# FPGA.net
KiCad netlist of a schematic drawn in Altium Designer
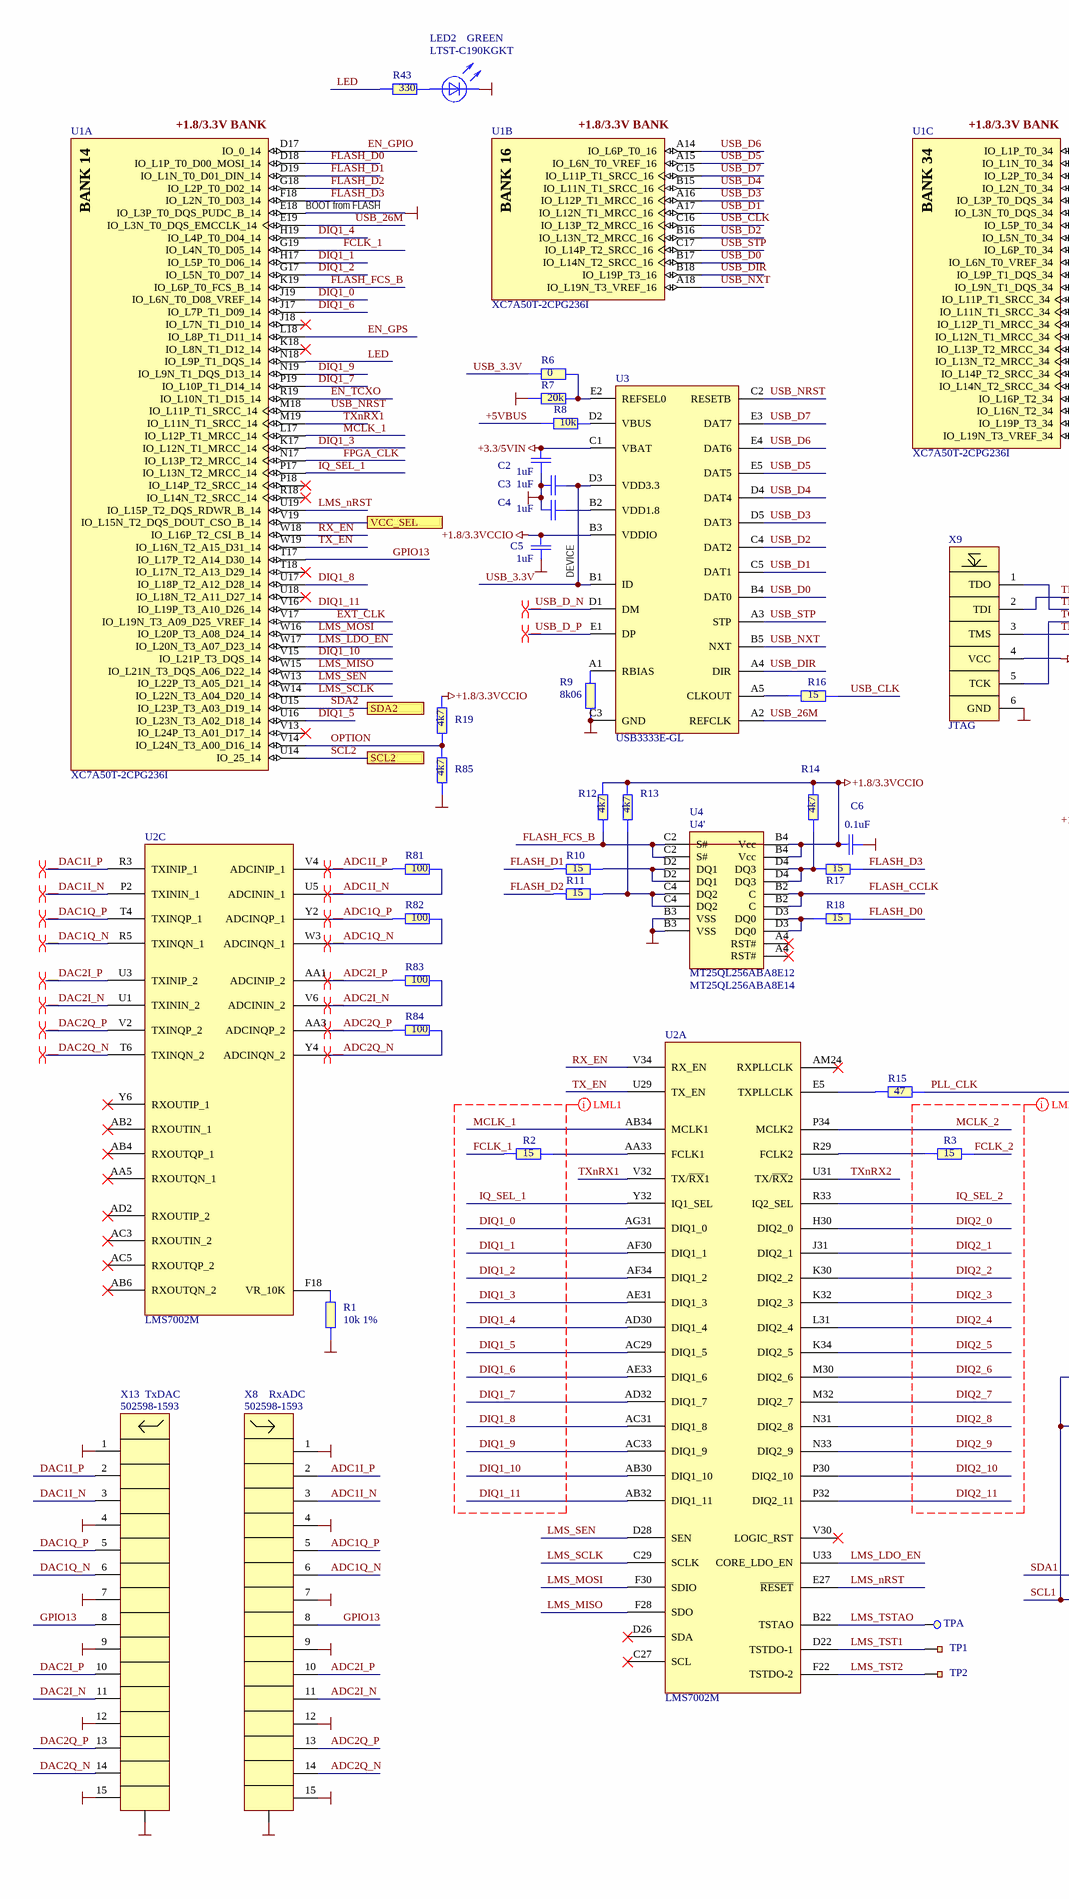
[diagram p0: FPGA.SchDoc, left]
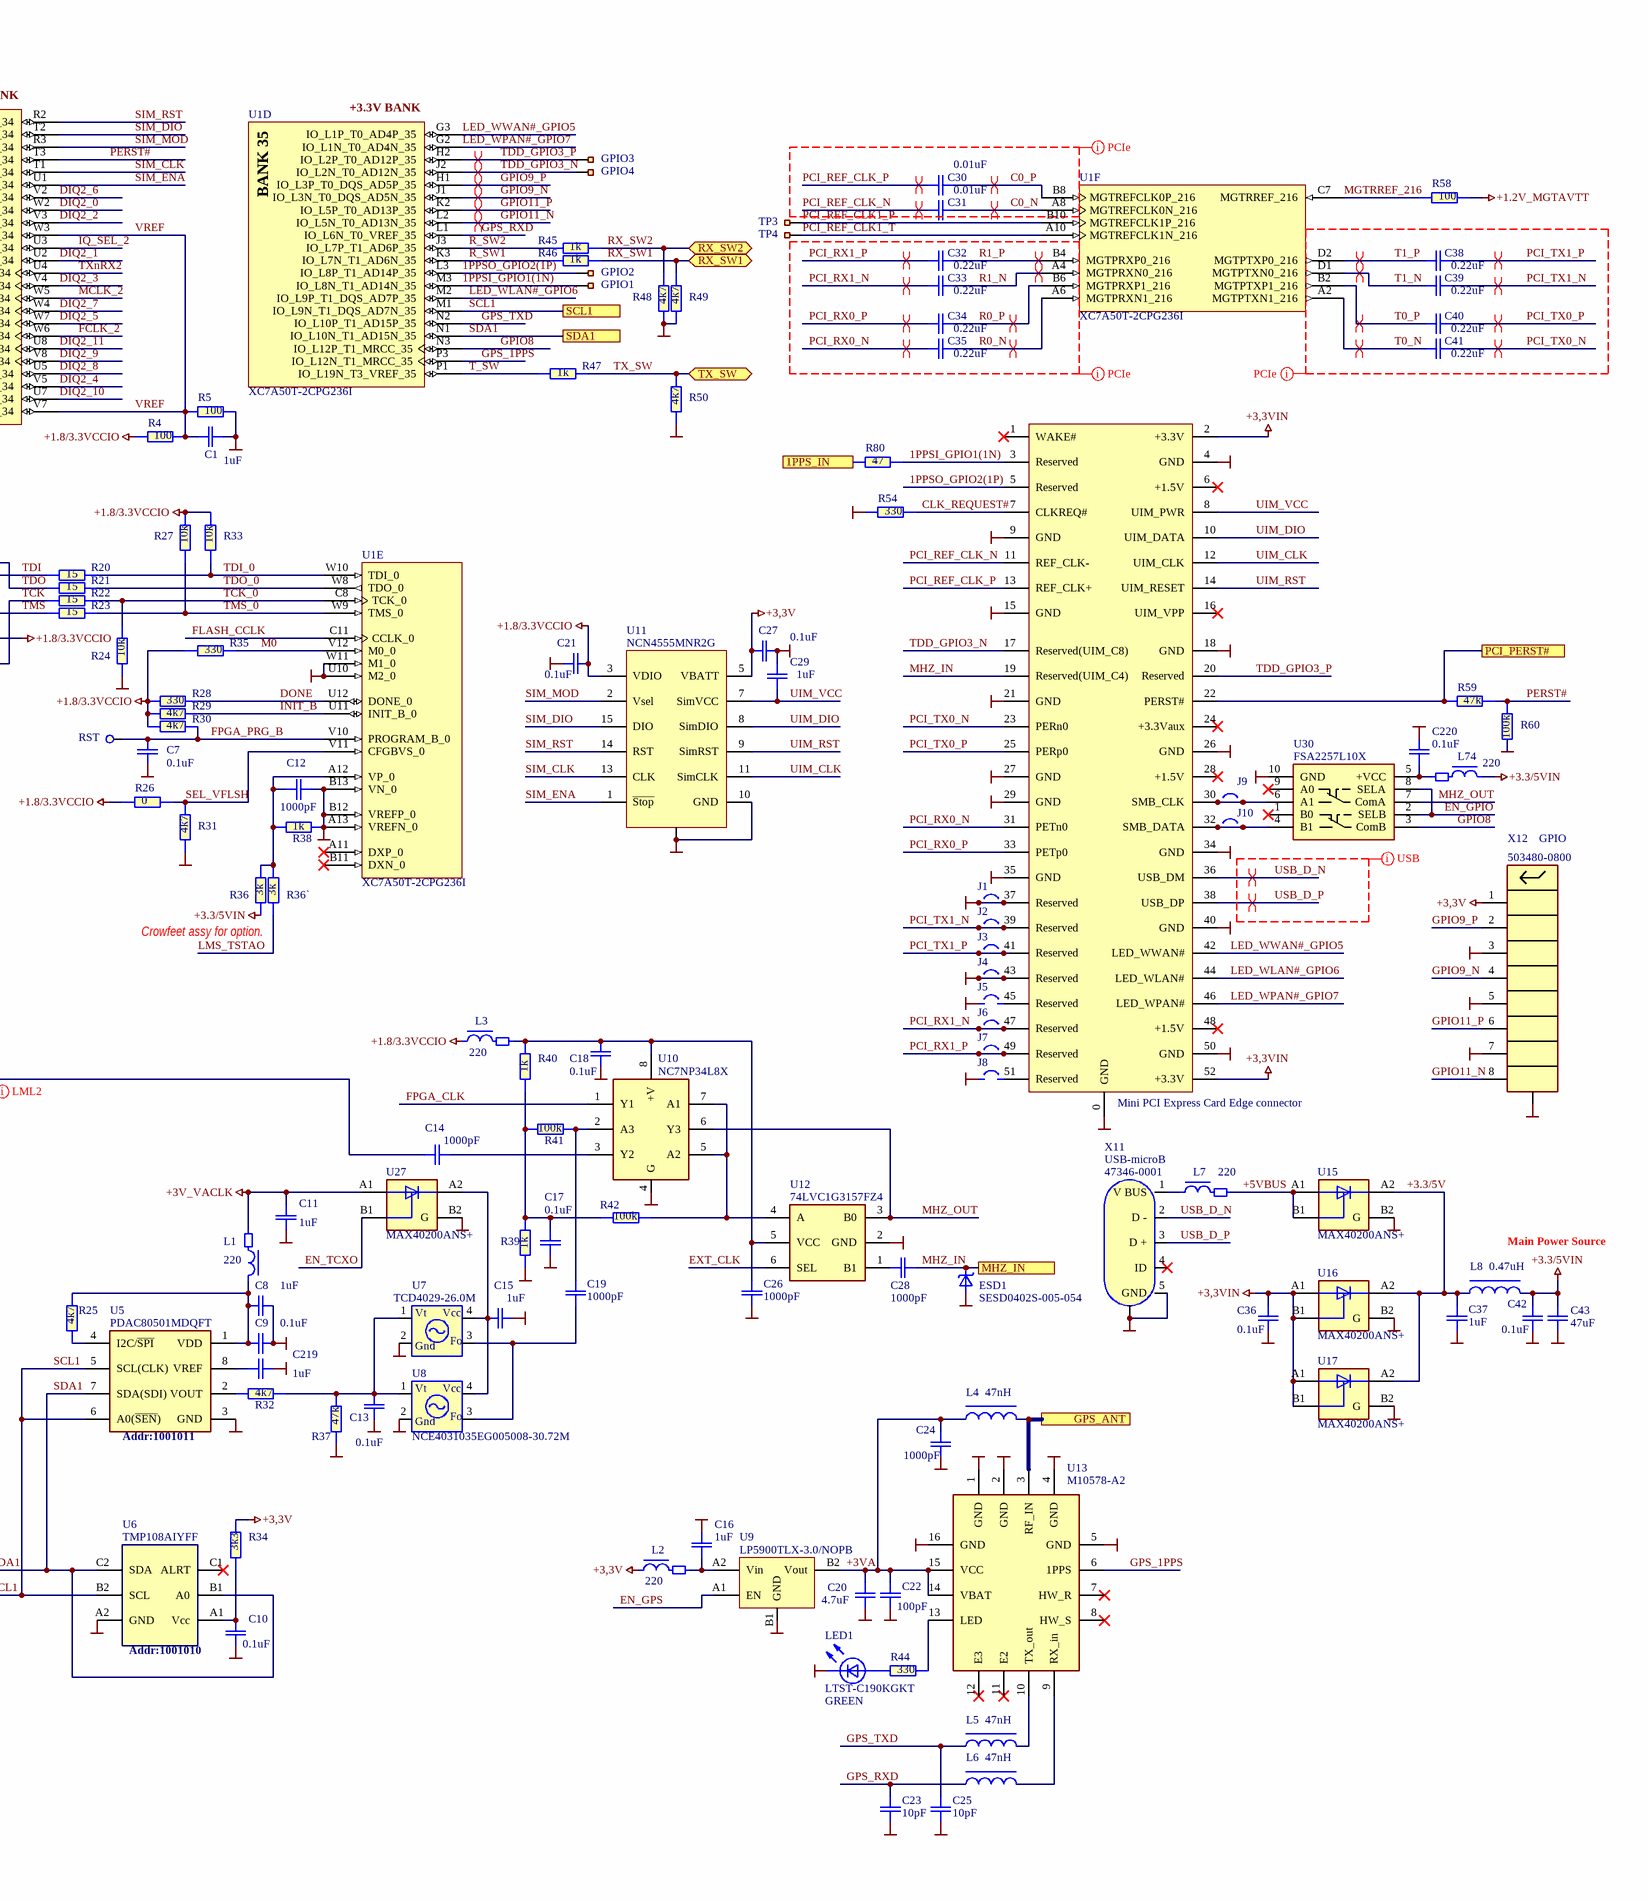
[diagram p1: FPGA.SchDoc, right]

(export (version "E")
  (design (tool "Eeschema 10.0.6"))
  (components
    (comp (ref "C1")
      (value "1uF")
      (footprint "C0402-cirq")
      (description "Capacitor")
      (fields (field (name "MANUFACTURER") "Any") (field (name "TOLERANCE") "20%"))
      (libsource (lib "Capacitors") (part "C0402"))
    )
    (comp (ref "C2")
      (value "1uF")
      (footprint "C0402-cirq")
      (description "Capacitor")
      (fields (field (name "MANUFACTURER") "Any") (field (name "TOLERANCE") "20%"))
      (libsource (lib "Capacitors") (part "C0402"))
    )
    (comp (ref "C3")
      (value "1uF")
      (footprint "C0402-cirq")
      (description "Capacitor")
      (fields (field (name "MANUFACTURER") "Any") (field (name "TOLERANCE") "20%"))
      (libsource (lib "Capacitors") (part "C0402"))
    )
    (comp (ref "C4")
      (value "1uF")
      (footprint "C0402-cirq")
      (description "Capacitor")
      (fields (field (name "MANUFACTURER") "Any") (field (name "TOLERANCE") "20%"))
      (libsource (lib "Capacitors") (part "C0402"))
    )
    (comp (ref "C5")
      (value "1uF")
      (footprint "C0402-cirq")
      (description "Capacitor")
      (fields (field (name "MANUFACTURER") "Any") (field (name "TOLERANCE") "20%"))
      (libsource (lib "Capacitors") (part "C0402"))
    )
    (comp (ref "C6")
      (value "0.1uF")
      (footprint "C0402-cirq")
      (description "Capacitor")
      (fields (field (name "MANUFACTURER") "Any") (field (name "TOLERANCE") "20%"))
      (libsource (lib "Capacitors") (part "C0402"))
    )
    (comp (ref "C7")
      (value "0.1uF")
      (footprint "C0402-cirq")
      (description "Capacitor")
      (fields (field (name "MANUFACTURER") "Any") (field (name "TOLERANCE") "20%"))
      (libsource (lib "Capacitors") (part "C0402"))
    )
    (comp (ref "C8")
      (value "1uF")
      (footprint "C0402-cirq")
      (description "Capacitor")
      (fields (field (name "MANUFACTURER") "Any") (field (name "TOLERANCE") "20%"))
      (libsource (lib "Capacitors") (part "C0402"))
    )
    (comp (ref "C9")
      (value "0.1uF")
      (footprint "C0402-cirq")
      (description "Capacitor")
      (fields (field (name "MANUFACTURER") "Any") (field (name "TOLERANCE") "20%"))
      (libsource (lib "Capacitors") (part "C0402"))
    )
    (comp (ref "C10")
      (value "0.1uF")
      (footprint "C0402-cirq")
      (description "Capacitor")
      (fields (field (name "MANUFACTURER") "Any") (field (name "TOLERANCE") "20%"))
      (libsource (lib "Capacitors") (part "C0402"))
    )
    (comp (ref "C11")
      (value "1uF")
      (footprint "C0402-cirq")
      (description "Capacitor")
      (fields (field (name "MANUFACTURER") "Any") (field (name "TOLERANCE") "20%"))
      (libsource (lib "Capacitors") (part "C0402"))
    )
    (comp (ref "C12")
      (value "1000pF")
      (footprint "C0402-cirq")
      (description "Capacitor")
      (fields (field (name "MANUFACTURER") "Any") (field (name "TOLERANCE") "10%"))
      (libsource (lib "Capacitors") (part "C0402"))
    )
    (comp (ref "C13")
      (value "0.1uF")
      (footprint "C0402-cirq")
      (description "Capacitor")
      (fields (field (name "MANUFACTURER") "Any") (field (name "TOLERANCE") "20%"))
      (libsource (lib "Capacitors") (part "C0402"))
    )
    (comp (ref "C14")
      (value "1000pF")
      (footprint "C0402-cirq")
      (description "Capacitor")
      (fields (field (name "MANUFACTURER") "Any") (field (name "TOLERANCE") "10%"))
      (libsource (lib "Capacitors") (part "C0402"))
    )
    (comp (ref "C15")
      (value "1uF")
      (footprint "C0402-cirq")
      (description "Capacitor")
      (fields (field (name "MANUFACTURER") "Any") (field (name "TOLERANCE") "20%"))
      (libsource (lib "Capacitors") (part "C0402"))
    )
    (comp (ref "C16")
      (value "1uF")
      (footprint "C0402-cirq")
      (description "Capacitor")
      (fields (field (name "MANUFACTURER") "Any") (field (name "TOLERANCE") "20%"))
      (libsource (lib "Capacitors") (part "C0402"))
    )
    (comp (ref "C17")
      (value "0.1uF")
      (footprint "C0402-cirq")
      (description "Capacitor")
      (fields (field (name "MANUFACTURER") "Any") (field (name "TOLERANCE") "20%"))
      (libsource (lib "Capacitors") (part "C0402"))
    )
    (comp (ref "C18")
      (value "0.1uF")
      (footprint "C0402-cirq")
      (description "Capacitor")
      (fields (field (name "MANUFACTURER") "Any") (field (name "TOLERANCE") "20%"))
      (libsource (lib "Capacitors") (part "C0402"))
    )
    (comp (ref "C19")
      (value "1000pF")
      (footprint "C0402-cirq")
      (description "Capacitor")
      (fields (field (name "MANUFACTURER") "Any") (field (name "TOLERANCE") "10%"))
      (libsource (lib "Capacitors") (part "C0402"))
    )
    (comp (ref "C20")
      (value "4.7uF")
      (footprint "C0402-cirq")
      (description "Capacitor")
      (fields (field (name "MANUFACTURER") "Any") (field (name "TOLERANCE") "20%"))
      (libsource (lib "Capacitors") (part "C0402"))
    )
    (comp (ref "C21")
      (value "0.1uF")
      (footprint "C0402-cirq")
      (description "Capacitor")
      (fields (field (name "MANUFACTURER") "Any") (field (name "TOLERANCE") "20%"))
      (libsource (lib "Capacitors") (part "C0402"))
    )
    (comp (ref "C22")
      (value "100pF")
      (footprint "C0402-cirq")
      (description "Capacitor")
      (fields (field (name "MANUFACTURER") "Any") (field (name "TOLERANCE") "20%"))
      (libsource (lib "Capacitors") (part "C0402"))
    )
    (comp (ref "C23")
      (value "10pF")
      (footprint "C0402-cirq")
      (description "Capacitor")
      (fields (field (name "MANUFACTURER") "Any") (field (name "TOLERANCE") "20%"))
      (libsource (lib "Capacitors") (part "C0402"))
    )
    (comp (ref "C24")
      (value "1000pF")
      (footprint "C0402-cirq")
      (description "Capacitor")
      (fields (field (name "MANUFACTURER") "Any") (field (name "TOLERANCE") "10%"))
      (libsource (lib "Capacitors") (part "C0402"))
    )
    (comp (ref "C25")
      (value "10pF")
      (footprint "C0402-cirq")
      (description "Capacitor")
      (fields (field (name "MANUFACTURER") "Any") (field (name "TOLERANCE") "20%"))
      (libsource (lib "Capacitors") (part "C0402"))
    )
    (comp (ref "C26")
      (value "1000pF")
      (footprint "C0402-cirq")
      (description "Capacitor")
      (fields (field (name "MANUFACTURER") "Any") (field (name "TOLERANCE") "10%"))
      (libsource (lib "Capacitors") (part "C0402"))
    )
    (comp (ref "C27")
      (value "0.1uF")
      (footprint "C0402-cirq")
      (description "Capacitor")
      (fields (field (name "MANUFACTURER") "Any") (field (name "TOLERANCE") "20%"))
      (libsource (lib "Capacitors") (part "C0402"))
    )
    (comp (ref "C28")
      (value "1000pF")
      (footprint "C0402-cirq")
      (description "Capacitor")
      (fields (field (name "MANUFACTURER") "Any") (field (name "TOLERANCE") "10%"))
      (libsource (lib "Capacitors") (part "C0402"))
    )
    (comp (ref "C29")
      (value "1uF")
      (footprint "C0402-cirq")
      (description "Capacitor")
      (fields (field (name "MANUFACTURER") "Any") (field (name "TOLERANCE") "20%"))
      (libsource (lib "Capacitors") (part "C0402"))
    )
    (comp (ref "C30")
      (value "0.01uF")
      (footprint "C0402-cirq")
      (description "Capacitor")
      (fields (field (name "MANUFACTURER") "Any") (field (name "TOLERANCE") "10%"))
      (libsource (lib "Capacitors") (part "C0402"))
    )
    (comp (ref "C31")
      (value "0.01uF")
      (footprint "C0402-cirq")
      (description "Capacitor")
      (fields (field (name "MANUFACTURER") "Any") (field (name "TOLERANCE") "10%"))
      (libsource (lib "Capacitors") (part "C0402"))
    )
    (comp (ref "C32")
      (value "0.22uF")
      (footprint "C0402-cirq")
      (description "Capacitor")
      (fields (field (name "MANUFACTURER") "Any") (field (name "TOLERANCE") "20%"))
      (libsource (lib "Capacitors") (part "C0402"))
    )
    (comp (ref "C33")
      (value "0.22uF")
      (footprint "C0402-cirq")
      (description "Capacitor")
      (fields (field (name "MANUFACTURER") "Any") (field (name "TOLERANCE") "20%"))
      (libsource (lib "Capacitors") (part "C0402"))
    )
    (comp (ref "C34")
      (value "0.22uF")
      (footprint "C0402-cirq")
      (description "Capacitor")
      (fields (field (name "MANUFACTURER") "Any") (field (name "TOLERANCE") "20%"))
      (libsource (lib "Capacitors") (part "C0402"))
    )
    (comp (ref "C35")
      (value "0.22uF")
      (footprint "C0402-cirq")
      (description "Capacitor")
      (fields (field (name "MANUFACTURER") "Any") (field (name "TOLERANCE") "20%"))
      (libsource (lib "Capacitors") (part "C0402"))
    )
    (comp (ref "C36")
      (value "0.1uF")
      (footprint "C0402-cirq")
      (description "Capacitor")
      (fields (field (name "MANUFACTURER") "Any") (field (name "TOLERANCE") "20%"))
      (libsource (lib "Capacitors") (part "C0402"))
    )
    (comp (ref "C37")
      (value "1uF")
      (footprint "C0402-cirq")
      (description "Capacitor")
      (fields (field (name "MANUFACTURER") "Any") (field (name "TOLERANCE") "20%"))
      (libsource (lib "Capacitors") (part "C0402"))
    )
    (comp (ref "C38")
      (value "0.22uF")
      (footprint "C0402-cirq")
      (description "Capacitor")
      (fields (field (name "MANUFACTURER") "Any") (field (name "TOLERANCE") "20%"))
      (libsource (lib "Capacitors") (part "C0402"))
    )
    (comp (ref "C39")
      (value "0.22uF")
      (footprint "C0402-cirq")
      (description "Capacitor")
      (fields (field (name "MANUFACTURER") "Any") (field (name "TOLERANCE") "20%"))
      (libsource (lib "Capacitors") (part "C0402"))
    )
    (comp (ref "C40")
      (value "0.22uF")
      (footprint "C0402-cirq")
      (description "Capacitor")
      (fields (field (name "MANUFACTURER") "Any") (field (name "TOLERANCE") "20%"))
      (libsource (lib "Capacitors") (part "C0402"))
    )
    (comp (ref "C41")
      (value "0.22uF")
      (footprint "C0402-cirq")
      (description "Capacitor")
      (fields (field (name "MANUFACTURER") "Any") (field (name "TOLERANCE") "20%"))
      (libsource (lib "Capacitors") (part "C0402"))
    )
    (comp (ref "C42")
      (value "0.1uF")
      (footprint "C0402-cirq")
      (description "Capacitor")
      (fields (field (name "MANUFACTURER") "Any") (field (name "TOLERANCE") "20%"))
      (libsource (lib "Capacitors") (part "C0402"))
    )
    (comp (ref "C43")
      (value "47uF")
      (footprint "C0603 tall")
      (description "Capacitor")
      (fields (field (name "MANUFACTURER") "MuRata") (field (name "TOLERANCE") "20%"))
      (libsource (lib "Andy") (part "C0603-TALL"))
    )
    (comp (ref "C219")
      (value "1uF")
      (footprint "C0402-cirq")
      (description "Capacitor")
      (fields (field (name "MANUFACTURER") "Any") (field (name "TOLERANCE") "20%"))
      (libsource (lib "Capacitors") (part "C0402"))
    )
    (comp (ref "C220")
      (value "0.1uF")
      (footprint "C0402-cirq")
      (description "Capacitor")
      (fields (field (name "MANUFACTURER") "Any") (field (name "TOLERANCE") "20%"))
      (libsource (lib "Capacitors") (part "C0402"))
    )
    (comp (ref "ESD1")
      (value "SESD0402S-005-054")
      (footprint "SESD0402-Phillips")
      (description "ESD diod unidirectional")
      (fields (field (name "MANUFACTURER") "Tyco Electronics Corp"))
      (libsource (lib "Andy") (part "SESD0402S"))
    )
    (comp (ref "GPIO1")
      (value "~")
      (footprint "KP-C_d1mm")
      (fields (field (name "MANUFACTURER") "PCB"))
      (libsource (lib "") (part "KP40X40_1"))
    )
    (comp (ref "GPIO2")
      (value "~")
      (footprint "KP-C_d1mm")
      (fields (field (name "MANUFACTURER") "PCB"))
      (libsource (lib "") (part "KP40X40_1"))
    )
    (comp (ref "GPIO3")
      (value "~")
      (footprint "KP-C_d1mm")
      (fields (field (name "MANUFACTURER") "PCB"))
      (libsource (lib "") (part "KP40X40_1"))
    )
    (comp (ref "GPIO4")
      (value "~")
      (footprint "KP-C_d1mm")
      (fields (field (name "MANUFACTURER") "PCB"))
      (libsource (lib "") (part "KP40X40_1"))
    )
    (comp (ref "J1")
      (value "~")
      (footprint "Andy:Jumper solder")
      (description "Manually soldered jumper")
      (fields (field (name "MANUFACTURER") "DIY"))
      (libsource (lib "Andy") (part "JUMPER PCB"))
    )
    (comp (ref "J2")
      (value "~")
      (footprint "Andy:Jumper solder")
      (description "Manually soldered jumper")
      (fields (field (name "MANUFACTURER") "DIY"))
      (libsource (lib "Andy") (part "JUMPER PCB"))
    )
    (comp (ref "J3")
      (value "~")
      (footprint "Andy:Jumper solder")
      (description "Manually soldered jumper")
      (fields (field (name "MANUFACTURER") "DIY"))
      (libsource (lib "Andy") (part "JUMPER PCB"))
    )
    (comp (ref "J4")
      (value "~")
      (footprint "Andy:Jumper solder")
      (description "Manually soldered jumper")
      (fields (field (name "MANUFACTURER") "DIY"))
      (libsource (lib "Andy") (part "JUMPER PCB"))
    )
    (comp (ref "J5")
      (value "~")
      (footprint "Andy:Jumper solder")
      (description "Manually soldered jumper")
      (fields (field (name "MANUFACTURER") "DIY"))
      (libsource (lib "Andy") (part "JUMPER PCB"))
    )
    (comp (ref "J6")
      (value "~")
      (footprint "Andy:Jumper solder")
      (description "Manually soldered jumper")
      (fields (field (name "MANUFACTURER") "DIY"))
      (libsource (lib "Andy") (part "JUMPER PCB"))
    )
    (comp (ref "J7")
      (value "~")
      (footprint "Andy:Jumper solder")
      (description "Manually soldered jumper")
      (fields (field (name "MANUFACTURER") "DIY"))
      (libsource (lib "Andy") (part "JUMPER PCB"))
    )
    (comp (ref "J8")
      (value "~")
      (footprint "Andy:Jumper solder")
      (description "Manually soldered jumper")
      (fields (field (name "MANUFACTURER") "DIY"))
      (libsource (lib "Andy") (part "JUMPER PCB"))
    )
    (comp (ref "J9")
      (value "~")
      (footprint "Andy:Jumper solder")
      (description "Manually soldered jumper")
      (fields (field (name "MANUFACTURER") "DIY"))
      (libsource (lib "Andy") (part "JUMPER PCB"))
    )
    (comp (ref "J10")
      (value "~")
      (footprint "Andy:Jumper solder")
      (description "Manually soldered jumper")
      (fields (field (name "MANUFACTURER") "DIY"))
      (libsource (lib "Andy") (part "JUMPER PCB"))
    )
    (comp (ref "L1")
      (value "220")
      (footprint "BEAD0402-Phillips")
      (description "Ferrite bead EMIFIL")
      (fields (field (name "MANUFACTURER") "MURATA"))
      (libsource (lib "") (part "EMI BLM15_1"))
    )
    (comp (ref "L2")
      (value "220")
      (footprint "BEAD0402-Phillips")
      (description "Ferrite bead EMIFIL")
      (fields (field (name "MANUFACTURER") "MURATA"))
      (libsource (lib "Andy") (part "EMI BLM15"))
    )
    (comp (ref "L3")
      (value "220")
      (footprint "BEAD0402-Phillips")
      (description "Ferrite bead EMIFIL")
      (fields (field (name "MANUFACTURER") "MURATA"))
      (libsource (lib "Andy") (part "EMI BLM15"))
    )
    (comp (ref "L4")
      (value "47nH")
      (footprint "COIL0402-Phillips")
      (description "Coil wire wound")
      (fields (field (name "MANUFACTURER") "MuRata") (field (name "TOLERANCE") "±5%"))
      (libsource (lib "Andy") (part "L-LQW15"))
    )
    (comp (ref "L5")
      (value "47nH")
      (footprint "COIL0402-Phillips")
      (description "Coil wire wound")
      (fields (field (name "MANUFACTURER") "MuRata") (field (name "TOLERANCE") "±5%"))
      (libsource (lib "Andy") (part "L-LQW15"))
    )
    (comp (ref "L6")
      (value "47nH")
      (footprint "COIL0402-Phillips")
      (description "Coil wire wound")
      (fields (field (name "MANUFACTURER") "MuRata") (field (name "TOLERANCE") "±5%"))
      (libsource (lib "Andy") (part "L-LQW15"))
    )
    (comp (ref "L7")
      (value "220")
      (footprint "BEAD0402-Phillips")
      (description "Ferrite bead EMIFIL")
      (fields (field (name "MANUFACTURER") "MURATA"))
      (libsource (lib "Andy") (part "EMI BLM15"))
    )
    (comp (ref "L8")
      (value "0.47uH")
      (footprint "L-VLS201610HBX")
      (description "Coil")
      (fields (field (name "MANUFACTURER") "TDK"))
      (libsource (lib "Andy") (part "L-VLS20161xHBX-1"))
    )
    (comp (ref "L74")
      (value "220")
      (footprint "BEAD0402-Phillips")
      (description "Ferrite bead EMIFIL")
      (fields (field (name "MANUFACTURER") "MURATA"))
      (libsource (lib "") (part "EMI BLM15_1"))
    )
    (comp (ref "LED1")
      (value "LTST-C190KGKT")
      (footprint "Andy:LED-0603GR")
      (description "LED GREEN")
      (fields (field (name "MANUFACTURER") "Lite-On Inc") (field (name "MISC") "GREEN"))
      (libsource (lib "Andy") (part "LED0603GR_Lite-On"))
    )
    (comp (ref "LED2")
      (value "LTST-C190KGKT")
      (footprint "Andy:LED-0603GR")
      (description "LED GREEN")
      (fields (field (name "MANUFACTURER") "Lite-On Inc") (field (name "MISC") "GREEN"))
      (libsource (lib "Andy") (part "LED0603GR_Lite-On"))
    )
    (comp (ref "R1")
      (value "10k 1%")
      (footprint "R0402-Phillips")
      (description "Resistor")
      (fields (field (name "MANUFACTURER") "BOURNS") (field (name "TOLERANCE") "1%"))
      (libsource (lib "") (part "R0402_2"))
    )
    (comp (ref "R2")
      (value "15")
      (footprint "R0402-Phillips")
      (description "Resistor")
      (fields (field (name "MANUFACTURER") "BOURNS") (field (name "TOLERANCE") "5%"))
      (libsource (lib "Andy") (part "R0402"))
    )
    (comp (ref "R3")
      (value "15")
      (footprint "R0402-Phillips")
      (description "Resistor")
      (fields (field (name "MANUFACTURER") "BOURNS") (field (name "TOLERANCE") "5%"))
      (libsource (lib "Andy") (part "R0402"))
    )
    (comp (ref "R4")
      (value "100")
      (footprint "R0402-Phillips")
      (description "Resistor")
      (fields (field (name "MANUFACTURER") "BOURNS") (field (name "TOLERANCE") "5%"))
      (libsource (lib "Andy") (part "R0402"))
    )
    (comp (ref "R5")
      (value "100")
      (footprint "R0402-Phillips")
      (description "Resistor")
      (fields (field (name "MANUFACTURER") "BOURNS") (field (name "TOLERANCE") "5%"))
      (libsource (lib "Andy") (part "R0402"))
    )
    (comp (ref "R6")
      (value "0")
      (footprint "R0402-Phillips")
      (description "Resistor")
      (fields (field (name "MANUFACTURER") "BOURNS") (field (name "TOLERANCE") "5%"))
      (libsource (lib "Andy") (part "R0402"))
    )
    (comp (ref "R7")
      (value "20k")
      (footprint "R0402-Phillips")
      (description "Resistor")
      (fields (field (name "MANUFACTURER") "BOURNS") (field (name "TOLERANCE") "5%"))
      (libsource (lib "Andy") (part "R0402"))
    )
    (comp (ref "R8")
      (value "10k")
      (footprint "R0402-Phillips")
      (description "Resistor")
      (fields (field (name "MANUFACTURER") "BOURNS") (field (name "TOLERANCE") "5%"))
      (libsource (lib "Andy") (part "R0402"))
    )
    (comp (ref "R9")
      (value "8k06")
      (footprint "R0402-Phillips")
      (description "Resistor")
      (fields (field (name "MANUFACTURER") "Panasonic") (field (name "TOLERANCE") "0.5%"))
      (libsource (lib "") (part "R0402_2"))
    )
    (comp (ref "R10")
      (value "15")
      (footprint "R0402-Phillips")
      (description "Resistor")
      (fields (field (name "MANUFACTURER") "BOURNS") (field (name "TOLERANCE") "5%"))
      (libsource (lib "") (part "R0402_3"))
    )
    (comp (ref "R11")
      (value "15")
      (footprint "R0402-Phillips")
      (description "Resistor")
      (fields (field (name "MANUFACTURER") "BOURNS") (field (name "TOLERANCE") "5%"))
      (libsource (lib "") (part "R0402_3"))
    )
    (comp (ref "R12")
      (value "4k7")
      (footprint "R0402-Phillips")
      (description "Resistor")
      (fields (field (name "MANUFACTURER") "BOURNS") (field (name "TOLERANCE") "5%"))
      (libsource (lib "") (part "R0402_1"))
    )
    (comp (ref "R13")
      (value "4k7")
      (footprint "R0402-Phillips")
      (description "Resistor")
      (fields (field (name "MANUFACTURER") "BOURNS") (field (name "TOLERANCE") "5%"))
      (libsource (lib "") (part "R0402_1"))
    )
    (comp (ref "R14")
      (value "4k7")
      (footprint "R0402-Phillips")
      (description "Resistor")
      (fields (field (name "MANUFACTURER") "BOURNS") (field (name "TOLERANCE") "5%"))
      (libsource (lib "") (part "R0402_1"))
    )
    (comp (ref "R15")
      (value "47")
      (footprint "R0402-Phillips")
      (description "Resistor")
      (fields (field (name "MANUFACTURER") "BOURNS") (field (name "TOLERANCE") "5%"))
      (libsource (lib "Andy") (part "R0402"))
    )
    (comp (ref "R16")
      (value "15")
      (footprint "R0402-Phillips")
      (description "Resistor")
      (fields (field (name "MANUFACTURER") "BOURNS") (field (name "TOLERANCE") "5%"))
      (libsource (lib "Andy") (part "R0402"))
    )
    (comp (ref "R17")
      (value "15")
      (footprint "R0402-Phillips")
      (description "Resistor")
      (fields (field (name "MANUFACTURER") "BOURNS") (field (name "TOLERANCE") "5%"))
      (libsource (lib "") (part "R0402_3"))
    )
    (comp (ref "R18")
      (value "15")
      (footprint "R0402-Phillips")
      (description "Resistor")
      (fields (field (name "MANUFACTURER") "BOURNS") (field (name "TOLERANCE") "5%"))
      (libsource (lib "") (part "R0402_3"))
    )
    (comp (ref "R19")
      (value "4k7")
      (footprint "R0402-Phillips")
      (description "Resistor")
      (fields (field (name "MANUFACTURER") "BOURNS") (field (name "TOLERANCE") "5%"))
      (libsource (lib "") (part "R0402_1"))
    )
    (comp (ref "R20")
      (value "15")
      (footprint "R0402-Phillips")
      (description "Resistor")
      (fields (field (name "MANUFACTURER") "BOURNS") (field (name "TOLERANCE") "5%"))
      (libsource (lib "Andy") (part "R0402"))
    )
    (comp (ref "R21")
      (value "15")
      (footprint "R0402-Phillips")
      (description "Resistor")
      (fields (field (name "MANUFACTURER") "BOURNS") (field (name "TOLERANCE") "5%"))
      (libsource (lib "Andy") (part "R0402"))
    )
    (comp (ref "R22")
      (value "15")
      (footprint "R0402-Phillips")
      (description "Resistor")
      (fields (field (name "MANUFACTURER") "BOURNS") (field (name "TOLERANCE") "5%"))
      (libsource (lib "Andy") (part "R0402"))
    )
    (comp (ref "R23")
      (value "15")
      (footprint "R0402-Phillips")
      (description "Resistor")
      (fields (field (name "MANUFACTURER") "BOURNS") (field (name "TOLERANCE") "5%"))
      (libsource (lib "Andy") (part "R0402"))
    )
    (comp (ref "R24")
      (value "10k")
      (footprint "R0402-Phillips")
      (description "Resistor")
      (fields (field (name "MANUFACTURER") "BOURNS") (field (name "TOLERANCE") "5%"))
      (libsource (lib "") (part "R0402_1"))
    )
    (comp (ref "R25")
      (value "4k7")
      (footprint "R0402-Phillips")
      (description "Resistor")
      (fields (field (name "MANUFACTURER") "BOURNS") (field (name "TOLERANCE") "5%"))
      (libsource (lib "") (part "R0402_2"))
    )
    (comp (ref "R26")
      (value "0")
      (footprint "R0402-Phillips")
      (description "Resistor")
      (fields (field (name "MANUFACTURER") "BOURNS") (field (name "TOLERANCE") "5%"))
      (libsource (lib "Andy") (part "R0402"))
    )
    (comp (ref "R27")
      (value "10k")
      (footprint "R0402-Phillips")
      (description "Resistor")
      (fields (field (name "MANUFACTURER") "BOURNS") (field (name "TOLERANCE") "5%"))
      (libsource (lib "") (part "R0402_1"))
    )
    (comp (ref "R28")
      (value "330")
      (footprint "R0402-Phillips")
      (description "Resistor")
      (fields (field (name "MANUFACTURER") "BOURNS") (field (name "TOLERANCE") "5%"))
      (libsource (lib "Andy") (part "R0402"))
    )
    (comp (ref "R29")
      (value "4k7")
      (footprint "R0402-Phillips")
      (description "Resistor")
      (fields (field (name "MANUFACTURER") "BOURNS") (field (name "TOLERANCE") "5%"))
      (libsource (lib "Andy") (part "R0402"))
    )
    (comp (ref "R30")
      (value "4k7")
      (footprint "R0402-Phillips")
      (description "Resistor")
      (fields (field (name "MANUFACTURER") "BOURNS") (field (name "TOLERANCE") "5%"))
      (libsource (lib "Andy") (part "R0402"))
    )
    (comp (ref "R31")
      (value "4k7")
      (footprint "R0402-Phillips")
      (description "Resistor")
      (fields (field (name "MANUFACTURER") "BOURNS") (field (name "TOLERANCE") "5%"))
      (libsource (lib "") (part "R0402_2"))
    )
    (comp (ref "R32")
      (value "4k7")
      (footprint "R0402-Phillips")
      (description "Resistor")
      (fields (field (name "MANUFACTURER") "BOURNS") (field (name "TOLERANCE") "5%"))
      (libsource (lib "Andy") (part "R0402"))
    )
    (comp (ref "R33")
      (value "10k")
      (footprint "R0402-Phillips")
      (description "Resistor")
      (fields (field (name "MANUFACTURER") "BOURNS") (field (name "TOLERANCE") "5%"))
      (libsource (lib "") (part "R0402_1"))
    )
    (comp (ref "R34")
      (value "3k3")
      (footprint "R0402-Phillips")
      (description "Resistor")
      (fields (field (name "MANUFACTURER") "BOURNS") (field (name "TOLERANCE") "5%"))
      (libsource (lib "") (part "R0402_1"))
    )
    (comp (ref "R35")
      (value "330")
      (footprint "R0402-Phillips")
      (description "Resistor")
      (fields (field (name "MANUFACTURER") "BOURNS") (field (name "TOLERANCE") "5%"))
      (libsource (lib "Andy") (part "R0402"))
    )
    (comp (ref "R36")
      (value "3k")
      (footprint "R0402-Phillips")
      (description "Resistor")
      (fields (field (name "MANUFACTURER") "BOURNS") (field (name "TOLERANCE") "5%"))
      (libsource (lib "") (part "R0402_2"))
    )
    (comp (ref "R36`")
      (value "3k")
      (footprint "R0402-Phillips")
      (description "Resistor")
      (fields (field (name "MANUFACTURER") "BOURNS") (field (name "TOLERANCE") "5%"))
      (libsource (lib "") (part "R0402_2"))
    )
    (comp (ref "R37")
      (value "47k")
      (footprint "R0402-Phillips")
      (description "Resistor")
      (fields (field (name "MANUFACTURER") "BOURNS") (field (name "TOLERANCE") "5%"))
      (libsource (lib "") (part "R0402_2"))
    )
    (comp (ref "R38")
      (value "1k")
      (footprint "R0402-Phillips")
      (description "Resistor")
      (fields (field (name "MANUFACTURER") "BOURNS") (field (name "TOLERANCE") "5%"))
      (libsource (lib "Andy") (part "R0402"))
    )
    (comp (ref "R39")
      (value "1k")
      (footprint "R0402-Phillips")
      (description "Resistor")
      (fields (field (name "MANUFACTURER") "BOURNS") (field (name "TOLERANCE") "5%"))
      (libsource (lib "") (part "R0402_1"))
    )
    (comp (ref "R40")
      (value "1k")
      (footprint "R0402-Phillips")
      (description "Resistor")
      (fields (field (name "MANUFACTURER") "BOURNS") (field (name "TOLERANCE") "5%"))
      (libsource (lib "") (part "R0402_1"))
    )
    (comp (ref "R41")
      (value "100k")
      (footprint "R0402-Phillips")
      (description "Resistor")
      (fields (field (name "MANUFACTURER") "BOURNS") (field (name "TOLERANCE") "5%"))
      (libsource (lib "Andy") (part "R0402"))
    )
    (comp (ref "R42")
      (value "100k")
      (footprint "R0402-Phillips")
      (description "Resistor")
      (fields (field (name "MANUFACTURER") "BOURNS") (field (name "TOLERANCE") "5%"))
      (libsource (lib "") (part "R0402_3"))
    )
    (comp (ref "R43")
      (value "330")
      (footprint "R0402-Phillips")
      (description "Resistor")
      (fields (field (name "MANUFACTURER") "BOURNS") (field (name "TOLERANCE") "5%"))
      (libsource (lib "Andy") (part "R0402"))
    )
    (comp (ref "R44")
      (value "330")
      (footprint "R0402-Phillips")
      (description "Resistor")
      (fields (field (name "MANUFACTURER") "BOURNS") (field (name "TOLERANCE") "5%"))
      (libsource (lib "Andy") (part "R0402"))
    )
    (comp (ref "R45")
      (value "1k")
      (footprint "R0402-Phillips")
      (description "Resistor")
      (fields (field (name "MANUFACTURER") "BOURNS") (field (name "TOLERANCE") "5%"))
      (libsource (lib "Andy") (part "R0402"))
    )
    (comp (ref "R46")
      (value "1k")
      (footprint "R0402-Phillips")
      (description "Resistor")
      (fields (field (name "MANUFACTURER") "BOURNS") (field (name "TOLERANCE") "5%"))
      (libsource (lib "Andy") (part "R0402"))
    )
    (comp (ref "R47")
      (value "1k")
      (footprint "R0402-Phillips")
      (description "Resistor")
      (fields (field (name "MANUFACTURER") "BOURNS") (field (name "TOLERANCE") "5%"))
      (libsource (lib "Andy") (part "R0402"))
    )
    (comp (ref "R48")
      (value "4k7")
      (footprint "R0402-Phillips")
      (description "Resistor")
      (fields (field (name "MANUFACTURER") "BOURNS") (field (name "TOLERANCE") "5%"))
      (libsource (lib "") (part "R0402_1"))
    )
    (comp (ref "R49")
      (value "4k7")
      (footprint "R0402-Phillips")
      (description "Resistor")
      (fields (field (name "MANUFACTURER") "BOURNS") (field (name "TOLERANCE") "5%"))
      (libsource (lib "") (part "R0402_1"))
    )
    (comp (ref "R50")
      (value "4k7")
      (footprint "R0402-Phillips")
      (description "Resistor")
      (fields (field (name "MANUFACTURER") "BOURNS") (field (name "TOLERANCE") "5%"))
      (libsource (lib "") (part "R0402_1"))
    )
    (comp (ref "R54")
      (value "330")
      (footprint "R0402-Phillips")
      (description "Resistor")
      (fields (field (name "MANUFACTURER") "BOURNS") (field (name "TOLERANCE") "5%"))
      (libsource (lib "Andy") (part "R0402"))
    )
    (comp (ref "R58")
      (value "100")
      (footprint "R0402-Phillips")
      (description "Resistor")
      (fields (field (name "MANUFACTURER") "BOURNS") (field (name "TOLERANCE") "1%"))
      (libsource (lib "Andy") (part "R0402"))
    )
    (comp (ref "R59")
      (value "47k")
      (footprint "R0402-Phillips")
      (description "Resistor")
      (fields (field (name "MANUFACTURER") "BOURNS") (field (name "TOLERANCE") "5%"))
      (libsource (lib "Andy") (part "R0402"))
    )
    (comp (ref "R60")
      (value "100k")
      (footprint "R0402-Phillips")
      (description "Resistor")
      (fields (field (name "MANUFACTURER") "BOURNS") (field (name "TOLERANCE") "5%"))
      (libsource (lib "") (part "R0402_1"))
    )
    (comp (ref "R80")
      (value "47")
      (footprint "R0402-Phillips")
      (description "Resistor")
      (fields (field (name "MANUFACTURER") "BOURNS") (field (name "TOLERANCE") "5%"))
      (libsource (lib "Andy") (part "R0402"))
    )
    (comp (ref "R81")
      (value "100")
      (footprint "R0402-Phillips")
      (description "Resistor")
      (fields (field (name "MANUFACTURER") "BOURNS") (field (name "TOLERANCE") "1%"))
      (libsource (lib "Andy") (part "R0402"))
    )
    (comp (ref "R82")
      (value "100")
      (footprint "R0402-Phillips")
      (description "Resistor")
      (fields (field (name "MANUFACTURER") "BOURNS") (field (name "TOLERANCE") "1%"))
      (libsource (lib "Andy") (part "R0402"))
    )
    (comp (ref "R83")
      (value "100")
      (footprint "R0402-Phillips")
      (description "Resistor")
      (fields (field (name "MANUFACTURER") "BOURNS") (field (name "TOLERANCE") "1%"))
      (libsource (lib "Andy") (part "R0402"))
    )
    (comp (ref "R84")
      (value "100")
      (footprint "R0402-Phillips")
      (description "Resistor")
      (fields (field (name "MANUFACTURER") "BOURNS") (field (name "TOLERANCE") "1%"))
      (libsource (lib "Andy") (part "R0402"))
    )
    (comp (ref "R85")
      (value "4k7")
      (footprint "R0402-Phillips")
      (description "Resistor")
      (fields (field (name "MANUFACTURER") "BOURNS") (field (name "TOLERANCE") "5%"))
      (libsource (lib "") (part "R0402_1"))
    )
    (comp (ref "RST")
      (value "~")
      (footprint "KP D1.5mm")
      (fields (field (name "MANUFACTURER") "PCB"))
      (libsource (lib "Connectors") (part "KP-D1.5mm"))
    )
    (comp (ref "TP1")
      (value "~")
      (footprint "KP-C_d1mm")
      (fields (field (name "MANUFACTURER") "PCB"))
      (libsource (lib "") (part "KP40X40_1"))
    )
    (comp (ref "TP2")
      (value "~")
      (footprint "KP-C_d1mm")
      (fields (field (name "MANUFACTURER") "PCB"))
      (libsource (lib "") (part "KP40X40_1"))
    )
    (comp (ref "TP3")
      (value "~")
      (footprint "KP-C_d1mm")
      (fields (field (name "MANUFACTURER") "PCB"))
      (libsource (lib "Connectors") (part "KP40X40"))
    )
    (comp (ref "TP4")
      (value "~")
      (footprint "KP-C_d1mm")
      (fields (field (name "MANUFACTURER") "PCB"))
      (libsource (lib "Connectors") (part "KP40X40"))
    )
    (comp (ref "TPA")
      (value "~")
      (footprint "KP D1.5mm")
      (fields (field (name "MANUFACTURER") "PCB"))
      (libsource (lib "Connectors") (part "KP-D1.5mm"))
    )
    (comp (ref "U1")
      (value "XC7A50T-2CPG236I")
      (footprint "CPG236")
      (description "Artix-7 FPGA")
      (fields (field (name "MANUFACTURER") "Xilinx"))
      (libsource (lib "Xilinx Artix-7") (part "XC7A35T-2CPG236C"))
    )
    (comp (ref "U2")
      (value "LMS7002M")
      (footprint "Andy:aQFN260(11.5x11.5mm)")
      (description "FPRF MIMO Transceiver IC")
      (fields (field (name "MANUFACTURER") "Lime Microsystems"))
      (libsource (lib "Andy") (part "LMS7002M"))
    )
    (comp (ref "U3")
      (value "USB3333E-GL")
      (footprint "Andy:BGA WLCSP25")
      (description "IC USB 2.0 FHY")
      (fields (field (name "MANUFACTURER") "Microchip"))
      (libsource (lib "Andy") (part "USB3333E-GL"))
    )
    (comp (ref "U4")
      (value "MT25QL256ABA8E12")
      (footprint "BGA T-BGA25 (6X8/1.0)")
      (description "IC NOR FLASH")
      (fields (field (name "MANUFACTURER") "Micron"))
      (libsource (lib "Andy") (part "MT25QL(U)256_BGA-12"))
    )
    (comp (ref "U4'")
      (value "MT25QL256ABA8E14")
      (footprint "BGA T-BGA24 (6X8/1.0)")
      (description "IC NOR FLASH")
      (fields (field (name "MANUFACTURER") "Micron"))
      (libsource (lib "Andy") (part "MT25QL(U)256_BGA-14"))
    )
    (comp (ref "U5")
      (value "PDAC80501MDQFT")
      (footprint "PWSON8 no PAD")
      (description "IC serial DAC")
      (fields (field (name "MANUFACTURER") "TI"))
      (libsource (lib "Andy") (part "DAC80501"))
    )
    (comp (ref "U6")
      (value "TMP108AIYFF")
      (footprint "BGA WCSP6")
      (description "IC Thermosensor")
      (fields (field (name "MANUFACTURER") "TI"))
      (libsource (lib "Andy") (part "TMP108"))
    )
    (comp (ref "U7")
      (value "TCD4029-26.0M")
      (footprint "TCXO5X3.2")
      (description "TCVCXO")
      (fields (field (name "MANUFACTURER") "Pletronics"))
      (libsource (lib "Andy") (part "TCVCXO_5x3.2"))
    )
    (comp (ref "U8")
      (value "NCE4031035EG005008-30.72M")
      (footprint "TCXO3.2X2.5")
      (description "TCVCXO")
      (fields (field (name "MANUFACTURER") "Pletronics"))
      (libsource (lib "Andy") (part "TCVCXO_2.5x3.2"))
    )
    (comp (ref "U9")
      (value "LP5900TLX-3.0/NOPB")
      (footprint "BGA DSBGA-4")
      (description "IC")
      (fields (field (name "MANUFACTURER") "TI"))
      (libsource (lib "Andy") (part "LP5900TL"))
    )
    (comp (ref "U10")
      (value "NC7NP34L8X")
      (footprint "Micro pak 8 (1.6x1.6/0.5)")
      (description "IC Triple Buffer")
      (fields (field (name "MANUFACTURER") "Fairchild"))
      (libsource (lib "Andy") (part "NC7NP34L8X"))
    )
    (comp (ref "U11")
      (value "NCN4555MNR2G")
      (footprint "QFN16(3x3/0/5mm)-Case485AE")
      (description "IC SIM Card buffer")
      (fields (field (name "MANUFACTURER") "ON Semi"))
      (libsource (lib "Andy") (part "NCN4555MN"))
    )
    (comp (ref "U12")
      (value "74LVC1G3157FZ4")
      (footprint "X2-DFN1410-6(1.4x1/0.5mm)")
      (description "IC SPDT switch")
      (fields (field (name "MANUFACTURER") "Diodes"))
      (libsource (lib "Andy") (part "74LVC1G3157"))
    )
    (comp (ref "U13")
      (value "M10578-A2")
      (footprint "Andy:GPS_M10578-Ax")
      (description "Module GPS resceiver")
      (fields (field (name "MANUFACTURER") "Radionova (Antenova)"))
      (libsource (lib "Andy") (part "GPS_M10578-Ax"))
    )
    (comp (ref "U15")
      (value "MAX40200ANS+")
      (footprint "BGA WLP4 (0.7x0.7/0.35)")
      (description "IC ideal diode switch")
      (fields (field (name "MANUFACTURER") "MAXIM"))
      (libsource (lib "Andy") (part "MAX40200ANS+"))
    )
    (comp (ref "U16")
      (value "MAX40200ANS+")
      (footprint "BGA WLP4 (0.7x0.7/0.35)")
      (description "IC ideal diode switch")
      (fields (field (name "MANUFACTURER") "MAXIM"))
      (libsource (lib "Andy") (part "MAX40200ANS+"))
    )
    (comp (ref "U17")
      (value "MAX40200ANS+")
      (footprint "BGA WLP4 (0.7x0.7/0.35)")
      (description "IC ideal diode switch")
      (fields (field (name "MANUFACTURER") "MAXIM"))
      (libsource (lib "Andy") (part "MAX40200ANS+"))
    )
    (comp (ref "U27")
      (value "MAX40200ANS+")
      (footprint "BGA WLP4 (0.7x0.7/0.35)")
      (description "IC ideal diode switch")
      (fields (field (name "MANUFACTURER") "MAXIM"))
      (libsource (lib "Andy") (part "MAX40200ANS+"))
    )
    (comp (ref "U30")
      (value "FSA2257L10X")
      (footprint "MICROPAK-10(2.1X1.6P0.5)")
      (description "IC dual SPDT bi-dir switch")
      (fields (field (name "MANUFACTURER") "Fairchild"))
      (libsource (lib "Andy") (part "FSA2257L10X"))
    )
    (comp (ref "X8")
      (value "502598-1593")
      (footprint "Molex 502598-1593")
      (description "Connector FFC/FPC")
      (fields (field (name "MANUFACTURER") "Molex") (field (name "ALTIUM_VALUE") "RxADC"))
      (libsource (lib "Andy") (part "Conn Molex 502598-1593"))
    )
    (comp (ref "X9")
      (value "JTAG")
      (footprint "Molex 78864-1001-Mating")
      (description "Connector for spring contacts")
      (fields (field (name "MANUFACTURER") "PCB"))
      (libsource (lib "Andy") (part "Conn Molex_788641001 mating"))
    )
    (comp (ref "X10")
      (value "Mini PCI Express Card Edge connector")
      (footprint "Andy:PCIe MiniCard")
      (description "PCIe MiniCard full or half size")
      (libsource (lib "Andy") (part "PCIe MiniCard"))
    )
    (comp (ref "X11")
      (value "USB-microB")
      (footprint "USB-microB")
      (description "Connector microUSB-B")
      (fields (field (name "ALTIUM_VALUE") "47346-0001") (field (name "MANUFACTURER") "Molex"))
      (libsource (lib "Andy") (part "USB-microB"))
    )
    (comp (ref "X12")
      (value "503480-0800")
      (footprint "Andy:Molex 503480-0800")
      (description "Connector FFC/FPC")
      (fields (field (name "MANUFACTURER") "Molex") (field (name "ALTIUM_VALUE") "GPIO"))
      (libsource (lib "Andy") (part "Conn Molex 503480-0800 one"))
    )
    (comp (ref "X13")
      (value "502598-1593")
      (footprint "Molex 502598-1593")
      (description "Connector FFC/FPC")
      (fields (field (name "MANUFACTURER") "Molex") (field (name "ALTIUM_VALUE") "TxDAC"))
      (libsource (lib "") (part "Conn Molex 502598-1593_1"))
    )
  )
  (nets
    (net (code "1") (name "+1.2V_MGTAVTT") (class "Default")
      (node (ref "R58") (pin "2") (pinfunction "2_2") (pintype "passive"))
    )
    (net (code "2") (name "+1.8{slash}3.3VCCIO") (class "Default")
      (node (ref "C21") (pin "2") (pinfunction "2_2") (pintype "passive"))
      (node (ref "C5") (pin "1") (pinfunction "1_1") (pintype "passive"))
      (node (ref "C6") (pin "2") (pinfunction "2_2") (pintype "passive"))
      (node (ref "L3") (pin "1") (pinfunction "1_1") (pintype "passive"))
      (node (ref "R12") (pin "2") (pinfunction "2_2") (pintype "passive"))
      (node (ref "R13") (pin "2") (pinfunction "2_2") (pintype "passive"))
      (node (ref "R14") (pin "2") (pinfunction "2_2") (pintype "passive"))
      (node (ref "R19") (pin "2") (pinfunction "2_2") (pintype "passive"))
      (node (ref "R26") (pin "1") (pinfunction "1_1") (pintype "passive"))
      (node (ref "R27") (pin "2") (pinfunction "2_2") (pintype "passive"))
      (node (ref "R28") (pin "1") (pinfunction "1_1") (pintype "passive"))
      (node (ref "R29") (pin "1") (pinfunction "1_1") (pintype "passive"))
      (node (ref "R30") (pin "1") (pinfunction "1_1") (pintype "passive"))
      (node (ref "R33") (pin "2") (pinfunction "2_2") (pintype "passive"))
      (node (ref "R35") (pin "1") (pinfunction "1_1") (pintype "passive"))
      (node (ref "R4") (pin "1") (pinfunction "1_1") (pintype "passive"))
      (node (ref "U11") (pin "3") (pinfunction "VDIO_3") (pintype "passive"))
      (node (ref "U3") (pin "B3") (pinfunction "VDDIO_B3") (pintype "passive"))
      (node (ref "U4") (pin "B4") (pinfunction "Vcc_B4") (pintype "passive"))
      (node (ref "U4'") (pin "B4") (pinfunction "Vcc_B4") (pintype "passive"))
      (node (ref "X9") (pin "4") (pinfunction "VCC_4") (pintype "passive"))
    )
    (net (code "3") (name "+3,3V") (class "Default")
      (node (ref "C27") (pin "2") (pinfunction "2_2") (pintype "passive"))
      (node (ref "L2") (pin "1") (pinfunction "1_1") (pintype "passive"))
      (node (ref "R34") (pin "2") (pinfunction "2_2") (pintype "passive"))
      (node (ref "U11") (pin "5") (pinfunction "VBATT_5") (pintype "passive"))
      (node (ref "X12") (pin "1") (pintype "passive"))
    )
    (net (code "4") (name "+3,3VIN") (class "Default")
      (node (ref "C36") (pin "2") (pinfunction "2_2") (pintype "passive"))
      (node (ref "U16") (pin "A1") (pinfunction "VDD_A1") (pintype "passive"))
      (node (ref "U16") (pin "B1") (pinfunction "EN_B1") (pintype "passive"))
      (node (ref "U17") (pin "A1") (pinfunction "VDD_A1") (pintype "passive"))
      (node (ref "U17") (pin "B1") (pinfunction "EN_B1") (pintype "passive"))
      (node (ref "X10") (pin "2") (pinfunction "+3.3V_2") (pintype "passive"))
      (node (ref "X10") (pin "52") (pinfunction "+3.3V_52") (pintype "passive"))
    )
    (net (code "5") (name "+3.3{slash}5VIN") (class "Default")
      (node (ref "C2") (pin "2") (pinfunction "2_2") (pintype "passive"))
      (node (ref "C42") (pin "2") (pinfunction "2_2") (pintype "passive"))
      (node (ref "C43") (pin "1") (pinfunction "1_1") (pintype "passive"))
      (node (ref "L74") (pin "1") (pinfunction "1_1") (pintype "passive"))
      (node (ref "L8") (pin "2") (pinfunction "2_2") (pintype "passive"))
      (node (ref "R36") (pin "2") (pinfunction "2_2") (pintype "passive"))
      (node (ref "U3") (pin "C1") (pinfunction "VBAT_C1") (pintype "passive"))
    )
    (net (code "6") (name "+3V_VACLK") (class "Default")
      (node (ref "C11") (pin "2") (pinfunction "2_2") (pintype "passive"))
      (node (ref "L1") (pin "2") (pinfunction "2_2") (pintype "passive"))
      (node (ref "U27") (pin "A1") (pinfunction "VDD_A1") (pintype "passive"))
    )
    (net (code "7") (name "/+3.3{slash}5V") (class "Default")
      (node (ref "C37") (pin "1") (pinfunction "1_1") (pintype "passive"))
      (node (ref "L8") (pin "1") (pinfunction "1_1") (pintype "passive"))
      (node (ref "U15") (pin "A2") (pinfunction "OUT_A2") (pintype "passive"))
      (node (ref "U16") (pin "A2") (pinfunction "OUT_A2") (pintype "passive"))
      (node (ref "U17") (pin "A2") (pinfunction "OUT_A2") (pintype "passive"))
    )
    (net (code "8") (name "/+3VA") (class "Default")
      (node (ref "C20") (pin "1") (pinfunction "1_1") (pintype "passive"))
      (node (ref "C22") (pin "2") (pinfunction "2_2") (pintype "passive"))
      (node (ref "C24") (pin "2") (pinfunction "2_2") (pintype "passive"))
      (node (ref "L4") (pin "1") (pinfunction "1_1") (pintype "passive"))
      (node (ref "U13") (pin "14") (pinfunction "VBAT_14") (pintype "passive"))
      (node (ref "U13") (pin "15") (pinfunction "VCC_15") (pintype "passive"))
      (node (ref "U9") (pin "B2") (pinfunction "Vout_B2") (pintype "passive"))
    )
    (net (code "9") (name "/+5VBUS") (class "Default")
      (node (ref "L7") (pin "2") (pinfunction "2_2") (pintype "passive"))
      (node (ref "R8") (pin "1") (pinfunction "1_1") (pintype "passive"))
      (node (ref "U15") (pin "A1") (pinfunction "VDD_A1") (pintype "passive"))
      (node (ref "U15") (pin "B1") (pinfunction "EN_B1") (pintype "passive"))
    )
    (net (code "10") (name "/1PPSI_GPIO1(1N)") (class "Default")
      (node (ref "GPIO1") (pin "1") (pinfunction "1_1") (pintype "passive"))
      (node (ref "R80") (pin "2") (pinfunction "2_2") (pintype "passive"))
      (node (ref "U1") (pin "M3") (pinfunction "IO_L8N_T1_AD14N_35_M3") (pintype "bidirectional"))
      (node (ref "X10") (pin "3") (pinfunction "Reserved_3") (pintype "passive"))
    )
    (net (code "11") (name "/1PPSO_GPIO2(1P)") (class "Default")
      (node (ref "GPIO2") (pin "1") (pinfunction "1_1") (pintype "passive"))
      (node (ref "U1") (pin "L3") (pinfunction "IO_L8P_T1_AD14P_35_L3") (pintype "bidirectional"))
      (node (ref "X10") (pin "5") (pinfunction "Reserved_5") (pintype "passive"))
    )
    (net (code "12") (name "/1PPS_IN") (class "Default")
      (node (ref "R80") (pin "1") (pinfunction "1_1") (pintype "passive"))
    )
    (net (code "13") (name "/ADC1I_N") (class "Default")
      (node (ref "R81") (pin "2") (pinfunction "2_2") (pintype "passive"))
      (node (ref "U2") (pin "U5") (pinfunction "ADCININ_1_U5") (pintype "passive"))
      (node (ref "X8") (pin "3") (pintype "passive"))
    )
    (net (code "14") (name "/ADC1I_P") (class "Default")
      (node (ref "R81") (pin "1") (pinfunction "1_1") (pintype "passive"))
      (node (ref "U2") (pin "V4") (pinfunction "ADCINIP_1_V4") (pintype "passive"))
      (node (ref "X8") (pin "2") (pintype "passive"))
    )
    (net (code "15") (name "/ADC1Q_N") (class "Default")
      (node (ref "R82") (pin "2") (pinfunction "2_2") (pintype "passive"))
      (node (ref "U2") (pin "W3") (pinfunction "ADCINQN_1_W3") (pintype "passive"))
      (node (ref "X8") (pin "6") (pintype "passive"))
    )
    (net (code "16") (name "/ADC1Q_P") (class "Default")
      (node (ref "R82") (pin "1") (pinfunction "1_1") (pintype "passive"))
      (node (ref "U2") (pin "Y2") (pinfunction "ADCINQP_1_Y2") (pintype "passive"))
      (node (ref "X8") (pin "5") (pintype "passive"))
    )
    (net (code "17") (name "/ADC2I_N") (class "Default")
      (node (ref "R83") (pin "2") (pinfunction "2_2") (pintype "passive"))
      (node (ref "U2") (pin "V6") (pinfunction "ADCININ_2_V6") (pintype "passive"))
      (node (ref "X8") (pin "11") (pintype "passive"))
    )
    (net (code "18") (name "/ADC2I_P") (class "Default")
      (node (ref "R83") (pin "1") (pinfunction "1_1") (pintype "passive"))
      (node (ref "U2") (pin "AA1") (pinfunction "ADCINIP_2_AA1") (pintype "passive"))
      (node (ref "X8") (pin "10") (pintype "passive"))
    )
    (net (code "19") (name "/ADC2Q_N") (class "Default")
      (node (ref "R84") (pin "2") (pinfunction "2_2") (pintype "passive"))
      (node (ref "U2") (pin "Y4") (pinfunction "ADCINQN_2_Y4") (pintype "passive"))
      (node (ref "X8") (pin "14") (pintype "passive"))
    )
    (net (code "20") (name "/ADC2Q_P") (class "Default")
      (node (ref "R84") (pin "1") (pinfunction "1_1") (pintype "passive"))
      (node (ref "U2") (pin "AA3") (pinfunction "ADCINQP_2_AA3") (pintype "passive"))
      (node (ref "X8") (pin "13") (pintype "passive"))
    )
    (net (code "21") (name "/C0_N") (class "Default")
      (node (ref "C31") (pin "2") (pinfunction "2_2") (pintype "passive"))
      (node (ref "U1") (pin "A8") (pinfunction "MGTREFCLK0N_216_A8") (pintype "input"))
    )
    (net (code "22") (name "/C0_P") (class "Default")
      (node (ref "C30") (pin "2") (pinfunction "2_2") (pintype "passive"))
      (node (ref "U1") (pin "B8") (pinfunction "MGTREFCLK0P_216_B8") (pintype "input"))
    )
    (net (code "23") (name "/CLK_REQUEST#") (class "Default")
      (node (ref "R54") (pin "2") (pinfunction "2_2") (pintype "passive"))
      (node (ref "X10") (pin "7") (pinfunction "CLKREQ#_7") (pintype "passive"))
    )
    (net (code "24") (name "/DAC1I_N") (class "Default")
      (node (ref "U2") (pin "P2") (pinfunction "TXININ_1_P2") (pintype "passive"))
      (node (ref "X13") (pin "3") (pintype "passive"))
    )
    (net (code "25") (name "/DAC1I_P") (class "Default")
      (node (ref "U2") (pin "R3") (pinfunction "TXINIP_1_R3") (pintype "passive"))
      (node (ref "X13") (pin "2") (pintype "passive"))
    )
    (net (code "26") (name "/DAC1Q_N") (class "Default")
      (node (ref "U2") (pin "R5") (pinfunction "TXINQN_1_R5") (pintype "passive"))
      (node (ref "X13") (pin "6") (pintype "passive"))
    )
    (net (code "27") (name "/DAC1Q_P") (class "Default")
      (node (ref "U2") (pin "T4") (pinfunction "TXINQP_1_T4") (pintype "passive"))
      (node (ref "X13") (pin "5") (pintype "passive"))
    )
    (net (code "28") (name "/DAC2I_N") (class "Default")
      (node (ref "U2") (pin "U1") (pinfunction "TXININ_2_U1") (pintype "passive"))
      (node (ref "X13") (pin "11") (pintype "passive"))
    )
    (net (code "29") (name "/DAC2I_P") (class "Default")
      (node (ref "U2") (pin "U3") (pinfunction "TXINIP_2_U3") (pintype "passive"))
      (node (ref "X13") (pin "10") (pintype "passive"))
    )
    (net (code "30") (name "/DAC2Q_N") (class "Default")
      (node (ref "U2") (pin "T6") (pinfunction "TXINQN_2_T6") (pintype "passive"))
      (node (ref "X13") (pin "14") (pintype "passive"))
    )
    (net (code "31") (name "/DAC2Q_P") (class "Default")
      (node (ref "U2") (pin "V2") (pinfunction "TXINQP_2_V2") (pintype "passive"))
      (node (ref "X13") (pin "13") (pintype "passive"))
    )
    (net (code "32") (name "/DIQ1_0") (class "Default")
      (node (ref "U1") (pin "J19") (pinfunction "IO_L6N_T0_D08_VREF_14_J19") (pintype "bidirectional"))
      (node (ref "U2") (pin "AG31") (pinfunction "DIQ1_0_AG31") (pintype "passive"))
    )
    (net (code "33") (name "/DIQ1_1") (class "Default")
      (node (ref "U1") (pin "H17") (pinfunction "IO_L5P_T0_D06_14_H17") (pintype "bidirectional"))
      (node (ref "U2") (pin "AF30") (pinfunction "DIQ1_1_AF30") (pintype "passive"))
    )
    (net (code "34") (name "/DIQ1_2") (class "Default")
      (node (ref "U1") (pin "G17") (pinfunction "IO_L5N_T0_D07_14_G17") (pintype "bidirectional"))
      (node (ref "U2") (pin "AF34") (pinfunction "DIQ1_2_AF34") (pintype "passive"))
    )
    (net (code "35") (name "/DIQ1_3") (class "Default")
      (node (ref "U1") (pin "K17") (pinfunction "IO_L12N_T1_MRCC_14_K17") (pintype "bidirectional"))
      (node (ref "U2") (pin "AE31") (pinfunction "DIQ1_3_AE31") (pintype "passive"))
    )
    (net (code "36") (name "/DIQ1_4") (class "Default")
      (node (ref "U1") (pin "H19") (pinfunction "IO_L4P_T0_D04_14_H19") (pintype "bidirectional"))
      (node (ref "U2") (pin "AD30") (pinfunction "DIQ1_4_AD30") (pintype "passive"))
    )
    (net (code "37") (name "/DIQ1_5") (class "Default")
      (node (ref "U1") (pin "U16") (pinfunction "IO_L23N_T3_A02_D18_14_U16") (pintype "bidirectional"))
      (node (ref "U2") (pin "AC29") (pinfunction "DIQ1_5_AC29") (pintype "passive"))
    )
    (net (code "38") (name "/DIQ1_6") (class "Default")
      (node (ref "U1") (pin "J17") (pinfunction "IO_L7P_T1_D09_14_J17") (pintype "bidirectional"))
      (node (ref "U2") (pin "AE33") (pinfunction "DIQ1_6_AE33") (pintype "passive"))
    )
    (net (code "39") (name "/DIQ1_7") (class "Default")
      (node (ref "U1") (pin "P19") (pinfunction "IO_L10P_T1_D14_14_P19") (pintype "bidirectional"))
      (node (ref "U2") (pin "AD32") (pinfunction "DIQ1_7_AD32") (pintype "passive"))
    )
    (net (code "40") (name "/DIQ1_8") (class "Default")
      (node (ref "U1") (pin "U17") (pinfunction "IO_L18P_T2_A12_D28_14_U17") (pintype "bidirectional"))
      (node (ref "U2") (pin "AC31") (pinfunction "DIQ1_8_AC31") (pintype "passive"))
    )
    (net (code "41") (name "/DIQ1_9") (class "Default")
      (node (ref "U1") (pin "N19") (pinfunction "IO_L9N_T1_DQS_D13_14_N19") (pintype "bidirectional"))
      (node (ref "U2") (pin "AC33") (pinfunction "DIQ1_9_AC33") (pintype "passive"))
    )
    (net (code "42") (name "/DIQ1_10") (class "Default")
      (node (ref "U1") (pin "V15") (pinfunction "IO_L21P_T3_DQS_14_V15") (pintype "bidirectional"))
      (node (ref "U2") (pin "AB30") (pinfunction "DIQ1_10_AB30") (pintype "passive"))
    )
    (net (code "43") (name "/DIQ1_11") (class "Default")
      (node (ref "U1") (pin "V16") (pinfunction "IO_L19P_T3_A10_D26_14_V16") (pintype "bidirectional"))
      (node (ref "U2") (pin "AB32") (pinfunction "DIQ1_11_AB32") (pintype "passive"))
    )
    (net (code "44") (name "/DIQ2_0") (class "Default")
      (node (ref "U1") (pin "W2") (pinfunction "IO_L5N_T0_34_W2") (pintype "bidirectional"))
      (node (ref "U2") (pin "H30") (pinfunction "DIQ2_0_H30") (pintype "passive"))
    )
    (net (code "45") (name "/DIQ2_1") (class "Default")
      (node (ref "U1") (pin "U2") (pinfunction "IO_L9N_T1_DQS_34_U2") (pintype "bidirectional"))
      (node (ref "U2") (pin "J31") (pinfunction "DIQ2_1_J31") (pintype "passive"))
    )
    (net (code "46") (name "/DIQ2_2") (class "Default")
      (node (ref "U1") (pin "V3") (pinfunction "IO_L6P_T0_34_V3") (pintype "bidirectional"))
      (node (ref "U2") (pin "K30") (pinfunction "DIQ2_2_K30") (pintype "passive"))
    )
    (net (code "47") (name "/DIQ2_3") (class "Default")
      (node (ref "U1") (pin "V4") (pinfunction "IO_L11N_T1_SRCC_34_V4") (pintype "bidirectional"))
      (node (ref "U2") (pin "K32") (pinfunction "DIQ2_3_K32") (pintype "passive"))
    )
    (net (code "48") (name "/DIQ2_4") (class "Default")
      (node (ref "U1") (pin "V5") (pinfunction "IO_L16N_T2_34_V5") (pintype "bidirectional"))
      (node (ref "U2") (pin "L31") (pinfunction "DIQ2_4_L31") (pintype "passive"))
    )
    (net (code "49") (name "/DIQ2_5") (class "Default")
      (node (ref "U1") (pin "W7") (pinfunction "IO_L13P_T2_MRCC_34_W7") (pintype "bidirectional"))
      (node (ref "U2") (pin "K34") (pinfunction "DIQ2_5_K34") (pintype "passive"))
    )
    (net (code "50") (name "/DIQ2_6") (class "Default")
      (node (ref "U1") (pin "V2") (pinfunction "IO_L5P_T0_34_V2") (pintype "bidirectional"))
      (node (ref "U2") (pin "M30") (pinfunction "DIQ2_6_M30") (pintype "passive"))
    )
    (net (code "51") (name "/DIQ2_7") (class "Default")
      (node (ref "U1") (pin "W4") (pinfunction "IO_L12N_T1_MRCC_34_W4") (pintype "bidirectional"))
      (node (ref "U2") (pin "M32") (pinfunction "DIQ2_7_M32") (pintype "passive"))
    )
    (net (code "52") (name "/DIQ2_8") (class "Default")
      (node (ref "U1") (pin "U5") (pinfunction "IO_L16P_T2_34_U5") (pintype "bidirectional"))
      (node (ref "U2") (pin "N31") (pinfunction "DIQ2_8_N31") (pintype "passive"))
    )
    (net (code "53") (name "/DIQ2_9") (class "Default")
      (node (ref "U1") (pin "V8") (pinfunction "IO_L14N_T2_SRCC_34_V8") (pintype "bidirectional"))
      (node (ref "U2") (pin "N33") (pinfunction "DIQ2_9_N33") (pintype "passive"))
    )
    (net (code "54") (name "/DIQ2_10") (class "Default")
      (node (ref "U1") (pin "U7") (pinfunction "IO_L19P_T3_34_U7") (pintype "bidirectional"))
      (node (ref "U2") (pin "P30") (pinfunction "DIQ2_10_P30") (pintype "passive"))
    )
    (net (code "55") (name "/DIQ2_11") (class "Default")
      (node (ref "U1") (pin "U8") (pinfunction "IO_L14P_T2_SRCC_34_U8") (pintype "bidirectional"))
      (node (ref "U2") (pin "P32") (pinfunction "DIQ2_11_P32") (pintype "passive"))
    )
    (net (code "56") (name "/DONE") (class "Default")
      (node (ref "R28") (pin "2") (pinfunction "2_2") (pintype "passive"))
      (node (ref "U1") (pin "U12") (pinfunction "DONE_0_U12") (pintype "bidirectional"))
    )
    (net (code "57") (name "/EN_GPIO") (class "Default")
      (node (ref "U1") (pin "D17") (pinfunction "IO_0_14_D17") (pintype "bidirectional"))
      (node (ref "U30") (pin "2") (pinfunction "SELB_2") (pintype "passive"))
      (node (ref "U30") (pin "8") (pinfunction "SELA_8") (pintype "passive"))
    )
    (net (code "58") (name "/EN_GPS") (class "Default")
      (node (ref "U1") (pin "L18") (pinfunction "IO_L8P_T1_D11_14_L18") (pintype "bidirectional"))
      (node (ref "U9") (pin "A1") (pinfunction "EN_A1") (pintype "passive"))
    )
    (net (code "59") (name "/EN_TCXO") (class "Default")
      (node (ref "U1") (pin "R19") (pinfunction "IO_L10N_T1_D15_14_R19") (pintype "bidirectional"))
      (node (ref "U27") (pin "B1") (pinfunction "EN_B1") (pintype "passive"))
    )
    (net (code "60") (name "/EXT_CLK") (class "Default")
      (node (ref "U1") (pin "V17") (pinfunction "IO_L19N_T3_A09_D25_VREF_14_V17") (pintype "bidirectional"))
      (node (ref "U12") (pin "6") (pinfunction "SEL_6") (pintype "passive"))
    )
    (net (code "61") (name "/FCLK_1") (class "Default")
      (node (ref "R2") (pin "1") (pinfunction "1_1") (pintype "passive"))
      (node (ref "U1") (pin "G19") (pinfunction "IO_L4N_T0_D05_14_G19") (pintype "bidirectional"))
    )
    (net (code "62") (name "/FCLK_2") (class "Default")
      (node (ref "R3") (pin "2") (pinfunction "2_2") (pintype "passive"))
      (node (ref "U1") (pin "W6") (pinfunction "IO_L13N_T2_MRCC_34_W6") (pintype "bidirectional"))
    )
    (net (code "63") (name "/FLASH_CCLK") (class "Default")
      (node (ref "U1") (pin "C11") (pinfunction "CCLK_0_C11") (pintype "input"))
      (node (ref "U4") (pin "B2") (pinfunction "C_B2") (pintype "passive"))
      (node (ref "U4'") (pin "B2") (pinfunction "C_B2") (pintype "passive"))
    )
    (net (code "64") (name "/FLASH_D0") (class "Default")
      (node (ref "R18") (pin "1") (pinfunction "1_1") (pintype "passive"))
      (node (ref "U1") (pin "D18") (pinfunction "IO_L1P_T0_D00_MOSI_14_D18") (pintype "bidirectional"))
    )
    (net (code "65") (name "/FLASH_D1") (class "Default")
      (node (ref "R10") (pin "2") (pinfunction "2_2") (pintype "passive"))
      (node (ref "U1") (pin "D19") (pinfunction "IO_L1N_T0_D01_DIN_14_D19") (pintype "bidirectional"))
    )
    (net (code "66") (name "/FLASH_D2") (class "Default")
      (node (ref "R11") (pin "2") (pinfunction "2_2") (pintype "passive"))
      (node (ref "U1") (pin "G18") (pinfunction "IO_L2P_T0_D02_14_G18") (pintype "bidirectional"))
    )
    (net (code "67") (name "/FLASH_D3") (class "Default")
      (node (ref "R17") (pin "1") (pinfunction "1_1") (pintype "passive"))
      (node (ref "U1") (pin "F18") (pinfunction "IO_L2N_T0_D03_14_F18") (pintype "bidirectional"))
    )
    (net (code "68") (name "/FLASH_FCS_B") (class "Default")
      (node (ref "R12") (pin "1") (pinfunction "1_1") (pintype "passive"))
      (node (ref "U1") (pin "K19") (pinfunction "IO_L6P_T0_FCS_B_14_K19") (pintype "bidirectional"))
      (node (ref "U4") (pin "C2") (pinfunction "S#_C2") (pintype "passive"))
      (node (ref "U4'") (pin "C2") (pinfunction "S#_C2") (pintype "passive"))
    )
    (net (code "69") (name "/FPGA_CLK") (class "Default")
      (node (ref "U1") (pin "N17") (pinfunction "IO_L13P_T2_MRCC_14_N17") (pintype "bidirectional"))
      (node (ref "U10") (pin "1") (pinfunction "Y1_1") (pintype "passive"))
    )
    (net (code "70") (name "/FPGA_PRG_B") (class "Default")
      (node (ref "C7") (pin "2") (pinfunction "2_2") (pintype "passive"))
      (node (ref "R30") (pin "2") (pinfunction "2_2") (pintype "passive"))
      (node (ref "RST") (pin "1") (pinfunction "1_1") (pintype "passive"))
      (node (ref "U1") (pin "V10") (pinfunction "PROGRAM_B_0_V10") (pintype "input"))
    )
    (net (code "71") (name "/GPIO8") (class "Default")
      (node (ref "U1") (pin "N3") (pinfunction "IO_L12P_T1_MRCC_35_N3") (pintype "bidirectional"))
      (node (ref "U30") (pin "3") (pinfunction "ComB_3") (pintype "passive"))
    )
    (net (code "72") (name "/GPIO9_N") (class "Default")
      (node (ref "U1") (pin "J1") (pinfunction "IO_L3N_T0_DQS_AD5N_35_J1") (pintype "bidirectional"))
      (node (ref "X12") (pin "4") (pintype "passive"))
    )
    (net (code "73") (name "/GPIO9_P") (class "Default")
      (node (ref "U1") (pin "H1") (pinfunction "IO_L3P_T0_DQS_AD5P_35_H1") (pintype "bidirectional"))
      (node (ref "X12") (pin "2") (pintype "passive"))
    )
    (net (code "74") (name "/GPIO11_N") (class "Default")
      (node (ref "U1") (pin "L2") (pinfunction "IO_L5N_T0_AD13N_35_L2") (pintype "bidirectional"))
      (node (ref "X12") (pin "8") (pintype "passive"))
    )
    (net (code "75") (name "/GPIO11_P") (class "Default")
      (node (ref "U1") (pin "K2") (pinfunction "IO_L5P_T0_AD13P_35_K2") (pintype "bidirectional"))
      (node (ref "X12") (pin "6") (pintype "passive"))
    )
    (net (code "76") (name "/GPIO13") (class "Default")
      (node (ref "U1") (pin "T17") (pinfunction "IO_L17P_T2_A14_D30_14_T17") (pintype "bidirectional"))
      (node (ref "X13") (pin "8") (pintype "passive"))
      (node (ref "X8") (pin "8") (pintype "passive"))
    )
    (net (code "77") (name "/GPS_1PPS") (class "Default")
      (node (ref "U1") (pin "P3") (pinfunction "IO_L12N_T1_MRCC_35_P3") (pintype "bidirectional"))
      (node (ref "U13") (pin "6") (pinfunction "1PPS_6") (pintype "passive"))
    )
    (net (code "78") (name "/GPS_ANT") (class "Default")
      (node (ref "L4") (pin "2") (pinfunction "2_2") (pintype "passive"))
      (node (ref "U13") (pin "3") (pinfunction "RF_IN_3") (pintype "passive"))
    )
    (net (code "79") (name "/GPS_RXD") (class "Default")
      (node (ref "C23") (pin "2") (pinfunction "2_2") (pintype "passive"))
      (node (ref "L6") (pin "1") (pinfunction "1_1") (pintype "passive"))
      (node (ref "U1") (pin "L1") (pinfunction "IO_L6N_T0_VREF_35_L1") (pintype "bidirectional"))
    )
    (net (code "80") (name "/GPS_TXD") (class "Default")
      (node (ref "C25") (pin "2") (pinfunction "2_2") (pintype "passive"))
      (node (ref "L5") (pin "1") (pinfunction "1_1") (pintype "passive"))
      (node (ref "U1") (pin "N2") (pinfunction "IO_L10P_T1_AD15P_35_N2") (pintype "bidirectional"))
    )
    (net (code "81") (name "/INIT_B") (class "Default")
      (node (ref "R29") (pin "2") (pinfunction "2_2") (pintype "passive"))
      (node (ref "U1") (pin "U11") (pinfunction "INIT_B_0_U11") (pintype "bidirectional"))
    )
    (net (code "82") (name "/IQ_SEL_1") (class "Default")
      (node (ref "U1") (pin "P17") (pinfunction "IO_L13N_T2_MRCC_14_P17") (pintype "bidirectional"))
      (node (ref "U2") (pin "Y32") (pinfunction "IQ1_SEL_Y32") (pintype "passive"))
    )
    (net (code "83") (name "/IQ_SEL_2") (class "Default")
      (node (ref "U1") (pin "U3") (pinfunction "IO_L9P_T1_DQS_34_U3") (pintype "bidirectional"))
      (node (ref "U2") (pin "R33") (pinfunction "IQ2_SEL_R33") (pintype "passive"))
    )
    (net (code "84") (name "/LED") (class "Default")
      (node (ref "R43") (pin "1") (pinfunction "1_1") (pintype "passive"))
      (node (ref "U1") (pin "N18") (pinfunction "IO_L9P_T1_DQS_14_N18") (pintype "bidirectional"))
    )
    (net (code "85") (name "/LED_WLAN#_GPIO6") (class "Default")
      (node (ref "U1") (pin "M2") (pinfunction "IO_L9P_T1_DQS_AD7P_35_M2") (pintype "bidirectional"))
      (node (ref "X10") (pin "44") (pinfunction "LED_WLAN#_44") (pintype "passive"))
    )
    (net (code "86") (name "/LED_WPAN#_GPIO7") (class "Default")
      (node (ref "U1") (pin "G2") (pinfunction "IO_L1N_T0_AD4N_35_G2") (pintype "bidirectional"))
      (node (ref "X10") (pin "46") (pinfunction "LED_WPAN#_46") (pintype "passive"))
    )
    (net (code "87") (name "/LED_WWAN#_GPIO5") (class "Default")
      (node (ref "U1") (pin "G3") (pinfunction "IO_L1P_T0_AD4P_35_G3") (pintype "bidirectional"))
      (node (ref "X10") (pin "42") (pinfunction "LED_WWAN#_42") (pintype "passive"))
    )
    (net (code "88") (name "/LMS_LDO_EN") (class "Default")
      (node (ref "U1") (pin "W17") (pinfunction "IO_L20N_T3_A07_D23_14_W17") (pintype "bidirectional"))
      (node (ref "U2") (pin "U33") (pinfunction "CORE_LDO_EN_U33") (pintype "passive"))
    )
    (net (code "89") (name "/LMS_MISO") (class "Default")
      (node (ref "U1") (pin "W15") (pinfunction "IO_L21N_T3_DQS_A06_D22_14_W15") (pintype "bidirectional"))
      (node (ref "U2") (pin "F28") (pinfunction "SDO_F28") (pintype "passive"))
    )
    (net (code "90") (name "/LMS_MOSI") (class "Default")
      (node (ref "U1") (pin "W16") (pinfunction "IO_L20P_T3_A08_D24_14_W16") (pintype "bidirectional"))
      (node (ref "U2") (pin "F30") (pinfunction "SDIO_F30") (pintype "passive"))
    )
    (net (code "91") (name "/LMS_SCLK") (class "Default")
      (node (ref "U1") (pin "W14") (pinfunction "IO_L22N_T3_A04_D20_14_W14") (pintype "bidirectional"))
      (node (ref "U2") (pin "C29") (pinfunction "SCLK_C29") (pintype "passive"))
    )
    (net (code "92") (name "/LMS_SEN") (class "Default")
      (node (ref "U1") (pin "W13") (pinfunction "IO_L22P_T3_A05_D21_14_W13") (pintype "bidirectional"))
      (node (ref "U2") (pin "D28") (pinfunction "SEN_D28") (pintype "passive"))
    )
    (net (code "93") (name "/LMS_TST1") (class "Default")
      (node (ref "TP1") (pin "1") (pinfunction "1_1") (pintype "passive"))
      (node (ref "U2") (pin "D22") (pinfunction "TSTDO-1_D22") (pintype "passive"))
    )
    (net (code "94") (name "/LMS_TST2") (class "Default")
      (node (ref "TP2") (pin "1") (pinfunction "1_1") (pintype "passive"))
      (node (ref "U2") (pin "F22") (pinfunction "TSTDO-2_F22") (pintype "passive"))
    )
    (net (code "95") (name "/LMS_TSTAO") (class "Default")
      (node (ref "R36`") (pin "2") (pinfunction "2_2") (pintype "passive"))
      (node (ref "TPA") (pin "1") (pinfunction "1_1") (pintype "passive"))
      (node (ref "U2") (pin "B22") (pinfunction "TSTAO_B22") (pintype "passive"))
    )
    (net (code "96") (name "/LMS_nRST") (class "Default")
      (node (ref "U1") (pin "U19") (pinfunction "IO_L15P_T2_DQS_RDWR_B_14_U19") (pintype "bidirectional"))
      (node (ref "U2") (pin "E27") (pinfunction "~{RESET}_E27") (pintype "passive"))
    )
    (net (code "97") (name "/M0") (class "Default")
      (node (ref "R35") (pin "2") (pinfunction "2_2") (pintype "passive"))
      (node (ref "U1") (pin "V12") (pinfunction "M0_0_V12") (pintype "input"))
    )
    (net (code "98") (name "/MCLK_1") (class "Default")
      (node (ref "U1") (pin "L17") (pinfunction "IO_L12P_T1_MRCC_14_L17") (pintype "bidirectional"))
      (node (ref "U2") (pin "AB34") (pinfunction "MCLK1_AB34") (pintype "passive"))
    )
    (net (code "99") (name "/MCLK_2") (class "Default")
      (node (ref "U1") (pin "W5") (pinfunction "IO_L12P_T1_MRCC_34_W5") (pintype "bidirectional"))
      (node (ref "U2") (pin "P34") (pinfunction "MCLK2_P34") (pintype "passive"))
    )
    (net (code "100") (name "/MGTRREF_216") (class "Default")
      (node (ref "R58") (pin "1") (pinfunction "1_1") (pintype "passive"))
      (node (ref "U1") (pin "C7") (pinfunction "MGTRREF_216_C7") (pintype "input"))
    )
    (net (code "101") (name "/MHZ_IN") (class "Default")
      (node (ref "C28") (pin "2") (pinfunction "2_2") (pintype "passive"))
      (node (ref "ESD1") (pin "1") (pinfunction "K_1") (pintype "passive"))
      (node (ref "X10") (pin "19") (pinfunction "Reserved(UIM_C4)_19") (pintype "passive"))
    )
    (net (code "102") (name "/MHZ_OUT") (class "Default")
      (node (ref "U10") (pin "6") (pinfunction "Y3_6") (pintype "passive"))
      (node (ref "U12") (pin "3") (pinfunction "B0_3") (pintype "passive"))
      (node (ref "U30") (pin "7") (pinfunction "ComA_7") (pintype "passive"))
    )
    (net (code "103") (name "/OPTION") (class "Default")
      (node (ref "R19") (pin "1") (pinfunction "1_1") (pintype "passive"))
      (node (ref "R85") (pin "2") (pinfunction "2_2") (pintype "passive"))
      (node (ref "U1") (pin "V14") (pinfunction "IO_L24N_T3_A00_D16_14_V14") (pintype "bidirectional"))
    )
    (net (code "104") (name "/PCI_PERST#") (class "Default")
      (node (ref "R59") (pin "1") (pinfunction "1_1") (pintype "passive"))
      (node (ref "X10") (pin "22") (pinfunction "PERST#_22") (pintype "passive"))
    )
    (net (code "105") (name "/PCI_REF_CLK1_P") (class "Default")
      (node (ref "TP3") (pin "1") (pinfunction "1_1") (pintype "passive"))
      (node (ref "U1") (pin "B10") (pinfunction "MGTREFCLK1P_216_B10") (pintype "input"))
    )
    (net (code "106") (name "/PCI_REF_CLK1_Т") (class "Default")
      (node (ref "TP4") (pin "1") (pinfunction "1_1") (pintype "passive"))
      (node (ref "U1") (pin "A10") (pinfunction "MGTREFCLK1N_216_A10") (pintype "input"))
    )
    (net (code "107") (name "/PCI_REF_CLK_N") (class "Default")
      (node (ref "C31") (pin "1") (pinfunction "1_1") (pintype "passive"))
      (node (ref "X10") (pin "11") (pinfunction "REF_CLK-_11") (pintype "passive"))
    )
    (net (code "108") (name "/PCI_REF_CLK_P") (class "Default")
      (node (ref "C30") (pin "1") (pinfunction "1_1") (pintype "passive"))
      (node (ref "X10") (pin "13") (pinfunction "REF_CLK+_13") (pintype "passive"))
    )
    (net (code "109") (name "/PCI_RX0_N") (class "Default")
      (node (ref "C35") (pin "1") (pinfunction "1_1") (pintype "passive"))
      (node (ref "X10") (pin "31") (pinfunction "PETn0_31") (pintype "passive"))
    )
    (net (code "110") (name "/PCI_RX0_P") (class "Default")
      (node (ref "C34") (pin "1") (pinfunction "1_1") (pintype "passive"))
      (node (ref "X10") (pin "33") (pinfunction "PETp0_33") (pintype "passive"))
    )
    (net (code "111") (name "/PCI_RX1_N") (class "Default")
      (node (ref "C33") (pin "1") (pinfunction "1_1") (pintype "passive"))
      (node (ref "J6") (pin "1") (pinfunction "1_1") (pintype "passive"))
      (node (ref "J6") (pin "2") (pinfunction "2_2") (pintype "passive"))
      (node (ref "X10") (pin "47") (pinfunction "Reserved_47") (pintype "passive"))
    )
    (net (code "112") (name "/PCI_RX1_P") (class "Default")
      (node (ref "C32") (pin "1") (pinfunction "1_1") (pintype "passive"))
      (node (ref "J7") (pin "1") (pinfunction "1_1") (pintype "passive"))
      (node (ref "J7") (pin "2") (pinfunction "2_2") (pintype "passive"))
      (node (ref "X10") (pin "49") (pinfunction "Reserved_49") (pintype "passive"))
    )
    (net (code "113") (name "/PCI_TX0_N") (class "Default")
      (node (ref "C41") (pin "2") (pinfunction "2_2") (pintype "passive"))
      (node (ref "X10") (pin "23") (pinfunction "PERn0_23") (pintype "passive"))
    )
    (net (code "114") (name "/PCI_TX0_P") (class "Default")
      (node (ref "C40") (pin "2") (pinfunction "2_2") (pintype "passive"))
      (node (ref "X10") (pin "25") (pinfunction "PERp0_25") (pintype "passive"))
    )
    (net (code "115") (name "/PCI_TX1_N") (class "Default")
      (node (ref "C39") (pin "2") (pinfunction "2_2") (pintype "passive"))
      (node (ref "J2") (pin "1") (pinfunction "1_1") (pintype "passive"))
      (node (ref "J2") (pin "2") (pinfunction "2_2") (pintype "passive"))
      (node (ref "X10") (pin "39") (pinfunction "Reserved_39") (pintype "passive"))
    )
    (net (code "116") (name "/PCI_TX1_P") (class "Default")
      (node (ref "C38") (pin "2") (pinfunction "2_2") (pintype "passive"))
      (node (ref "J3") (pin "1") (pinfunction "1_1") (pintype "passive"))
      (node (ref "J3") (pin "2") (pinfunction "2_2") (pintype "passive"))
      (node (ref "X10") (pin "41") (pinfunction "Reserved_41") (pintype "passive"))
    )
    (net (code "117") (name "/PERST#") (class "Default")
      (node (ref "R59") (pin "2") (pinfunction "2_2") (pintype "passive"))
      (node (ref "R60") (pin "2") (pinfunction "2_2") (pintype "passive"))
      (node (ref "U1") (pin "T3") (pinfunction "IO_L2N_T0_34_T3") (pintype "bidirectional"))
    )
    (net (code "118") (name "/PLL_CLK") (class "Default")
      (node (ref "C14") (pin "2") (pinfunction "2_2") (pintype "passive"))
      (node (ref "R15") (pin "2") (pinfunction "2_2") (pintype "passive"))
    )
    (net (code "119") (name "/R0_N") (class "Default")
      (node (ref "C35") (pin "2") (pinfunction "2_2") (pintype "passive"))
      (node (ref "U1") (pin "A6") (pinfunction "MGTPRXN1_216_A6") (pintype "input"))
    )
    (net (code "120") (name "/R0_P") (class "Default")
      (node (ref "C34") (pin "2") (pinfunction "2_2") (pintype "passive"))
      (node (ref "U1") (pin "B6") (pinfunction "MGTPRXP1_216_B6") (pintype "input"))
    )
    (net (code "121") (name "/R1_N") (class "Default")
      (node (ref "C33") (pin "2") (pinfunction "2_2") (pintype "passive"))
      (node (ref "U1") (pin "A4") (pinfunction "MGTPRXN0_216_A4") (pintype "input"))
    )
    (net (code "122") (name "/R1_P") (class "Default")
      (node (ref "C32") (pin "2") (pinfunction "2_2") (pintype "passive"))
      (node (ref "U1") (pin "B4") (pinfunction "MGTPRXP0_216_B4") (pintype "input"))
    )
    (net (code "123") (name "/RX_EN") (class "Default")
      (node (ref "U1") (pin "W18") (pinfunction "IO_L16P_T2_CSI_B_14_W18") (pintype "bidirectional"))
      (node (ref "U2") (pin "V34") (pinfunction "RX_EN_V34") (pintype "passive"))
    )
    (net (code "124") (name "/RX_SW1") (class "Default")
      (node (ref "R46") (pin "2") (pinfunction "2_2") (pintype "passive"))
      (node (ref "R49") (pin "2") (pinfunction "2_2") (pintype "passive"))
    )
    (net (code "125") (name "/RX_SW2") (class "Default")
      (node (ref "R45") (pin "2") (pinfunction "2_2") (pintype "passive"))
      (node (ref "R48") (pin "2") (pinfunction "2_2") (pintype "passive"))
    )
    (net (code "126") (name "/R_SW1") (class "Default")
      (node (ref "R46") (pin "1") (pinfunction "1_1") (pintype "passive"))
      (node (ref "U1") (pin "K3") (pinfunction "IO_L7N_T1_AD6N_35_K3") (pintype "bidirectional"))
    )
    (net (code "127") (name "/R_SW2") (class "Default")
      (node (ref "R45") (pin "1") (pinfunction "1_1") (pintype "passive"))
      (node (ref "U1") (pin "J3") (pinfunction "IO_L7P_T1_AD6P_35_J3") (pintype "bidirectional"))
    )
    (net (code "128") (name "/SCL1") (class "Default")
      (node (ref "U1") (pin "M1") (pinfunction "IO_L9N_T1_DQS_AD7N_35_M1") (pintype "bidirectional"))
      (node (ref "U5") (pin "5") (pinfunction "SCL(CLK)_5") (pintype "passive"))
      (node (ref "U5") (pin "6") (pinfunction "A0(~{SEN})_6") (pintype "passive"))
      (node (ref "U6") (pin "B2") (pinfunction "SCL_B2") (pintype "passive"))
    )
    (net (code "129") (name "/SCL2") (class "Default")
      (node (ref "U1") (pin "U14") (pinfunction "IO_25_14_U14") (pintype "bidirectional"))
    )
    (net (code "130") (name "/SDA1") (class "Default")
      (node (ref "U1") (pin "N1") (pinfunction "IO_L10N_T1_AD15N_35_N1") (pintype "bidirectional"))
      (node (ref "U5") (pin "7") (pinfunction "SDA(SDI)_7") (pintype "passive"))
      (node (ref "U6") (pin "B1") (pinfunction "A0_B1") (pintype "passive"))
      (node (ref "U6") (pin "C2") (pinfunction "SDA_C2") (pintype "passive"))
    )
    (net (code "131") (name "/SDA2") (class "Default")
      (node (ref "U1") (pin "U15") (pinfunction "IO_L23P_T3_A03_D19_14_U15") (pintype "bidirectional"))
    )
    (net (code "132") (name "/SEL_VFLSH") (class "Default")
      (node (ref "R26") (pin "2") (pinfunction "2_2") (pintype "passive"))
      (node (ref "R31") (pin "1") (pinfunction "1_1") (pintype "passive"))
      (node (ref "U1") (pin "V11") (pinfunction "CFGBVS_0_V11") (pintype "input"))
    )
    (net (code "133") (name "/SIM_CLK") (class "Default")
      (node (ref "U1") (pin "T1") (pinfunction "IO_L3P_T0_DQS_34_T1") (pintype "bidirectional"))
      (node (ref "U11") (pin "13") (pinfunction "CLK_13") (pintype "passive"))
    )
    (net (code "134") (name "/SIM_DIO") (class "Default")
      (node (ref "U1") (pin "T2") (pinfunction "IO_L1N_T0_34_T2") (pintype "bidirectional"))
      (node (ref "U11") (pin "15") (pinfunction "DIO_15") (pintype "passive"))
    )
    (net (code "135") (name "/SIM_ENA") (class "Default")
      (node (ref "U1") (pin "U1") (pinfunction "IO_L3N_T0_DQS_34_U1") (pintype "bidirectional"))
      (node (ref "U11") (pin "1") (pinfunction "~{Stop}_1") (pintype "passive"))
    )
    (net (code "136") (name "/SIM_MOD") (class "Default")
      (node (ref "U1") (pin "R3") (pinfunction "IO_L2P_T0_34_R3") (pintype "bidirectional"))
      (node (ref "U11") (pin "2") (pinfunction "Vsel_2") (pintype "passive"))
    )
    (net (code "137") (name "/SIM_RST") (class "Default")
      (node (ref "U1") (pin "R2") (pinfunction "IO_L1P_T0_34_R2") (pintype "bidirectional"))
      (node (ref "U11") (pin "14") (pinfunction "RST_14") (pintype "passive"))
    )
    (net (code "138") (name "/T0_N") (class "Default")
      (node (ref "C41") (pin "1") (pinfunction "1_1") (pintype "passive"))
      (node (ref "U1") (pin "A2") (pinfunction "MGTPTXN1_216_A2") (pintype "output"))
    )
    (net (code "139") (name "/T0_P") (class "Default")
      (node (ref "C40") (pin "1") (pinfunction "1_1") (pintype "passive"))
      (node (ref "U1") (pin "B2") (pinfunction "MGTPTXP1_216_B2") (pintype "output"))
    )
    (net (code "140") (name "/T1_N") (class "Default")
      (node (ref "C39") (pin "1") (pinfunction "1_1") (pintype "passive"))
      (node (ref "U1") (pin "D1") (pinfunction "MGTPTXN0_216_D1") (pintype "output"))
    )
    (net (code "141") (name "/T1_P") (class "Default")
      (node (ref "C38") (pin "1") (pinfunction "1_1") (pintype "passive"))
      (node (ref "U1") (pin "D2") (pinfunction "MGTPTXP0_216_D2") (pintype "output"))
    )
    (net (code "142") (name "/TCK") (class "Default")
      (node (ref "R22") (pin "1") (pinfunction "1_1") (pintype "passive"))
      (node (ref "X9") (pin "5") (pinfunction "TCK_5") (pintype "passive"))
    )
    (net (code "143") (name "/TCK_0") (class "Default")
      (node (ref "R22") (pin "2") (pinfunction "2_2") (pintype "passive"))
      (node (ref "R24") (pin "2") (pinfunction "2_2") (pintype "passive"))
      (node (ref "U1") (pin "C8") (pinfunction "TCK_0_C8") (pintype "input"))
    )
    (net (code "144") (name "/TDD_GPIO3_N") (class "Default")
      (node (ref "GPIO4") (pin "1") (pinfunction "1_1") (pintype "passive"))
      (node (ref "U1") (pin "J2") (pinfunction "IO_L2N_T0_AD12N_35_J2") (pintype "bidirectional"))
      (node (ref "X10") (pin "17") (pinfunction "Reserved(UIM_C8)_17") (pintype "passive"))
    )
    (net (code "145") (name "/TDD_GPIO3_P") (class "Default")
      (node (ref "GPIO3") (pin "1") (pinfunction "1_1") (pintype "passive"))
      (node (ref "U1") (pin "H2") (pinfunction "IO_L2P_T0_AD12P_35_H2") (pintype "bidirectional"))
      (node (ref "X10") (pin "20") (pinfunction "Reserved_20") (pintype "passive"))
    )
    (net (code "146") (name "/TDI") (class "Default")
      (node (ref "R20") (pin "1") (pinfunction "1_1") (pintype "passive"))
      (node (ref "X9") (pin "2") (pinfunction "TDI_2") (pintype "passive"))
    )
    (net (code "147") (name "/TDI_0") (class "Default")
      (node (ref "R20") (pin "2") (pinfunction "2_2") (pintype "passive"))
      (node (ref "R33") (pin "1") (pinfunction "1_1") (pintype "passive"))
      (node (ref "U1") (pin "W10") (pinfunction "TDI_0_W10") (pintype "input"))
    )
    (net (code "148") (name "/TDO") (class "Default")
      (node (ref "R21") (pin "1") (pinfunction "1_1") (pintype "passive"))
      (node (ref "X9") (pin "1") (pinfunction "TDO_1") (pintype "passive"))
    )
    (net (code "149") (name "/TDO_0") (class "Default")
      (node (ref "R21") (pin "2") (pinfunction "2_2") (pintype "passive"))
      (node (ref "U1") (pin "W8") (pinfunction "TDO_0_W8") (pintype "output"))
    )
    (net (code "150") (name "/TMS") (class "Default")
      (node (ref "R23") (pin "1") (pinfunction "1_1") (pintype "passive"))
      (node (ref "X9") (pin "3") (pinfunction "TMS_3") (pintype "passive"))
    )
    (net (code "151") (name "/TMS_0") (class "Default")
      (node (ref "R23") (pin "2") (pinfunction "2_2") (pintype "passive"))
      (node (ref "R27") (pin "1") (pinfunction "1_1") (pintype "passive"))
      (node (ref "U1") (pin "W9") (pinfunction "TMS_0_W9") (pintype "input"))
    )
    (net (code "152") (name "/TX_EN") (class "Default")
      (node (ref "U1") (pin "W19") (pinfunction "IO_L16N_T2_A15_D31_14_W19") (pintype "bidirectional"))
      (node (ref "U2") (pin "U29") (pinfunction "TX_EN_U29") (pintype "passive"))
    )
    (net (code "153") (name "/TX_SW") (class "Default")
      (node (ref "R47") (pin "2") (pinfunction "2_2") (pintype "passive"))
      (node (ref "R50") (pin "2") (pinfunction "2_2") (pintype "passive"))
    )
    (net (code "154") (name "/TXnRX1") (class "Default")
      (node (ref "U1") (pin "M19") (pinfunction "IO_L11N_T1_SRCC_14_M19") (pintype "bidirectional"))
      (node (ref "U2") (pin "V32") (pinfunction "TX/~{RX}1_V32") (pintype "passive"))
    )
    (net (code "155") (name "/TXnRX2") (class "Default")
      (node (ref "U1") (pin "U4") (pinfunction "IO_L11P_T1_SRCC_34_U4") (pintype "bidirectional"))
      (node (ref "U2") (pin "U31") (pinfunction "TX/~{RX}2_U31") (pintype "passive"))
    )
    (net (code "156") (name "/T_SW") (class "Default")
      (node (ref "R47") (pin "1") (pinfunction "1_1") (pintype "passive"))
      (node (ref "U1") (pin "P1") (pinfunction "IO_L19N_T3_VREF_35_P1") (pintype "bidirectional"))
    )
    (net (code "157") (name "/UIM_CLK") (class "Default")
      (node (ref "U11") (pin "11") (pinfunction "SimCLK_11") (pintype "passive"))
      (node (ref "X10") (pin "12") (pinfunction "UIM_CLK_12") (pintype "passive"))
    )
    (net (code "158") (name "/UIM_DIO") (class "Default")
      (node (ref "U11") (pin "8") (pinfunction "SimDIO_8") (pintype "passive"))
      (node (ref "X10") (pin "10") (pinfunction "UIM_DATA_10") (pintype "passive"))
    )
    (net (code "159") (name "/UIM_RST") (class "Default")
      (node (ref "U11") (pin "9") (pinfunction "SimRST_9") (pintype "passive"))
      (node (ref "X10") (pin "14") (pinfunction "UIM_RESET_14") (pintype "passive"))
    )
    (net (code "160") (name "/UIM_VCC") (class "Default")
      (node (ref "C29") (pin "1") (pinfunction "1_1") (pintype "passive"))
      (node (ref "U11") (pin "7") (pinfunction "SimVCC_7") (pintype "passive"))
      (node (ref "X10") (pin "8") (pinfunction "UIM_PWR_8") (pintype "passive"))
    )
    (net (code "161") (name "/USB_3.3V") (class "Default")
      (node (ref "C3") (pin "2") (pinfunction "2_2") (pintype "passive"))
      (node (ref "R6") (pin "1") (pinfunction "1_1") (pintype "passive"))
      (node (ref "U3") (pin "B1") (pinfunction "ID_B1") (pintype "passive"))
      (node (ref "U3") (pin "D3") (pinfunction "VDD3.3_D3") (pintype "passive"))
    )
    (net (code "162") (name "/USB_26M") (class "Default")
      (node (ref "U1") (pin "E19") (pinfunction "IO_L3N_T0_DQS_EMCCLK_14_E19") (pintype "bidirectional"))
      (node (ref "U3") (pin "A2") (pinfunction "REFCLK_A2") (pintype "passive"))
    )
    (net (code "163") (name "/USB_CLK") (class "Default")
      (node (ref "R16") (pin "2") (pinfunction "2_2") (pintype "passive"))
      (node (ref "U1") (pin "C16") (pinfunction "IO_L13P_T2_MRCC_16_C16") (pintype "bidirectional"))
    )
    (net (code "164") (name "/USB_D0") (class "Default")
      (node (ref "U1") (pin "B17") (pinfunction "IO_L14N_T2_SRCC_16_B17") (pintype "bidirectional"))
      (node (ref "U3") (pin "B4") (pinfunction "DAT0_B4") (pintype "passive"))
    )
    (net (code "165") (name "/USB_D1") (class "Default")
      (node (ref "U1") (pin "A17") (pinfunction "IO_L12N_T1_MRCC_16_A17") (pintype "bidirectional"))
      (node (ref "U3") (pin "C5") (pinfunction "DAT1_C5") (pintype "passive"))
    )
    (net (code "166") (name "/USB_D2") (class "Default")
      (node (ref "U1") (pin "B16") (pinfunction "IO_L13N_T2_MRCC_16_B16") (pintype "bidirectional"))
      (node (ref "U3") (pin "C4") (pinfunction "DAT2_C4") (pintype "passive"))
    )
    (net (code "167") (name "/USB_D3") (class "Default")
      (node (ref "U1") (pin "A16") (pinfunction "IO_L12P_T1_MRCC_16_A16") (pintype "bidirectional"))
      (node (ref "U3") (pin "D5") (pinfunction "DAT3_D5") (pintype "passive"))
    )
    (net (code "168") (name "/USB_D4") (class "Default")
      (node (ref "U1") (pin "B15") (pinfunction "IO_L11N_T1_SRCC_16_B15") (pintype "bidirectional"))
      (node (ref "U3") (pin "D4") (pinfunction "DAT4_D4") (pintype "passive"))
    )
    (net (code "169") (name "/USB_D5") (class "Default")
      (node (ref "U1") (pin "A15") (pinfunction "IO_L6N_T0_VREF_16_A15") (pintype "bidirectional"))
      (node (ref "U3") (pin "E5") (pinfunction "DAT5_E5") (pintype "passive"))
    )
    (net (code "170") (name "/USB_D6") (class "Default")
      (node (ref "U1") (pin "A14") (pinfunction "IO_L6P_T0_16_A14") (pintype "bidirectional"))
      (node (ref "U3") (pin "E4") (pinfunction "DAT6_E4") (pintype "passive"))
    )
    (net (code "171") (name "/USB_D7") (class "Default")
      (node (ref "U1") (pin "C15") (pinfunction "IO_L11P_T1_SRCC_16_C15") (pintype "bidirectional"))
      (node (ref "U3") (pin "E3") (pinfunction "DAT7_E3") (pintype "passive"))
    )
    (net (code "172") (name "/USB_DIR") (class "Default")
      (node (ref "U1") (pin "B18") (pinfunction "IO_L19P_T3_16_B18") (pintype "bidirectional"))
      (node (ref "U3") (pin "A4") (pinfunction "DIR_A4") (pintype "passive"))
    )
    (net (code "173") (name "/USB_D_N") (class "Default")
      (node (ref "U3") (pin "D1") (pinfunction "DM_D1") (pintype "passive"))
      (node (ref "X10") (pin "36") (pinfunction "USB_DM_36") (pintype "passive"))
      (node (ref "X11") (pin "2") (pinfunction "D_-_2") (pintype "passive"))
    )
    (net (code "174") (name "/USB_D_P") (class "Default")
      (node (ref "U3") (pin "E1") (pinfunction "DP_E1") (pintype "passive"))
      (node (ref "X10") (pin "38") (pinfunction "USB_DP_38") (pintype "passive"))
      (node (ref "X11") (pin "3") (pinfunction "D_+_3") (pintype "passive"))
    )
    (net (code "175") (name "/USB_NRST") (class "Default")
      (node (ref "U1") (pin "M18") (pinfunction "IO_L11P_T1_SRCC_14_M18") (pintype "bidirectional"))
      (node (ref "U3") (pin "C2") (pinfunction "RESETB_C2") (pintype "passive"))
    )
    (net (code "176") (name "/USB_NXT") (class "Default")
      (node (ref "U1") (pin "A18") (pinfunction "IO_L19N_T3_VREF_16_A18") (pintype "bidirectional"))
      (node (ref "U3") (pin "B5") (pinfunction "NXT_B5") (pintype "passive"))
    )
    (net (code "177") (name "/USB_STP") (class "Default")
      (node (ref "U1") (pin "C17") (pinfunction "IO_L14P_T2_SRCC_16_C17") (pintype "bidirectional"))
      (node (ref "U3") (pin "A3") (pinfunction "STP_A3") (pintype "passive"))
    )
    (net (code "178") (name "/VCC_SEL") (class "Default")
      (node (ref "U1") (pin "V19") (pinfunction "IO_L15N_T2_DQS_DOUT_CSO_B_14_V19") (pintype "bidirectional"))
    )
    (net (code "179") (name "/VREF") (class "Default")
      (node (ref "C1") (pin "2") (pinfunction "2_2") (pintype "passive"))
      (node (ref "R4") (pin "2") (pinfunction "2_2") (pintype "passive"))
      (node (ref "R5") (pin "1") (pinfunction "1_1") (pintype "passive"))
      (node (ref "U1") (pin "V7") (pinfunction "IO_L19N_T3_VREF_34_V7") (pintype "bidirectional"))
      (node (ref "U1") (pin "W3") (pinfunction "IO_L6N_T0_VREF_34_W3") (pintype "bidirectional"))
    )
    (net (code "180") (name "GND") (class "Default")
      (node (ref "C1") (pin "1") (pinfunction "1_1") (pintype "passive"))
      (node (ref "C10") (pin "2") (pinfunction "2_2") (pintype "passive"))
      (node (ref "C11") (pin "1") (pinfunction "1_1") (pintype "passive"))
      (node (ref "C12") (pin "1") (pinfunction "1_1") (pintype "passive"))
      (node (ref "C13") (pin "1") (pinfunction "1_1") (pintype "passive"))
      (node (ref "C15") (pin "1") (pinfunction "1_1") (pintype "passive"))
      (node (ref "C16") (pin "1") (pinfunction "1_1") (pintype "passive"))
      (node (ref "C17") (pin "2") (pinfunction "2_2") (pintype "passive"))
      (node (ref "C18") (pin "2") (pinfunction "2_2") (pintype "passive"))
      (node (ref "C2") (pin "1") (pinfunction "1_1") (pintype "passive"))
      (node (ref "C20") (pin "2") (pinfunction "2_2") (pintype "passive"))
      (node (ref "C21") (pin "1") (pinfunction "1_1") (pintype "passive"))
      (node (ref "C219") (pin "1") (pinfunction "1_1") (pintype "passive"))
      (node (ref "C22") (pin "1") (pinfunction "1_1") (pintype "passive"))
      (node (ref "C220") (pin "1") (pinfunction "1_1") (pintype "passive"))
      (node (ref "C23") (pin "1") (pinfunction "1_1") (pintype "passive"))
      (node (ref "C24") (pin "1") (pinfunction "1_1") (pintype "passive"))
      (node (ref "C25") (pin "1") (pinfunction "1_1") (pintype "passive"))
      (node (ref "C26") (pin "2") (pinfunction "2_2") (pintype "passive"))
      (node (ref "C27") (pin "1") (pinfunction "1_1") (pintype "passive"))
      (node (ref "C29") (pin "2") (pinfunction "2_2") (pintype "passive"))
      (node (ref "C3") (pin "1") (pinfunction "1_1") (pintype "passive"))
      (node (ref "C36") (pin "1") (pinfunction "1_1") (pintype "passive"))
      (node (ref "C37") (pin "2") (pinfunction "2_2") (pintype "passive"))
      (node (ref "C4") (pin "1") (pinfunction "1_1") (pintype "passive"))
      (node (ref "C42") (pin "1") (pinfunction "1_1") (pintype "passive"))
      (node (ref "C43") (pin "2") (pinfunction "2_2") (pintype "passive"))
      (node (ref "C5") (pin "2") (pinfunction "2_2") (pintype "passive"))
      (node (ref "C6") (pin "1") (pinfunction "1_1") (pintype "passive"))
      (node (ref "C7") (pin "1") (pinfunction "1_1") (pintype "passive"))
      (node (ref "C8") (pin "1") (pinfunction "1_1") (pintype "passive"))
      (node (ref "C9") (pin "1") (pinfunction "1_1") (pintype "passive"))
      (node (ref "ESD1") (pin "2") (pinfunction "A_2") (pintype "passive"))
      (node (ref "J1") (pin "1") (pinfunction "1_1") (pintype "passive"))
      (node (ref "J1") (pin "2") (pinfunction "2_2") (pintype "passive"))
      (node (ref "J4") (pin "1") (pinfunction "1_1") (pintype "passive"))
      (node (ref "J4") (pin "2") (pinfunction "2_2") (pintype "passive"))
      (node (ref "J5") (pin "2") (pinfunction "2_2") (pintype "passive"))
      (node (ref "J8") (pin "2") (pinfunction "2_2") (pintype "passive"))
      (node (ref "LED1") (pin "1") (pinfunction "K_1") (pintype "passive"))
      (node (ref "LED2") (pin "1") (pinfunction "K_1") (pintype "passive"))
      (node (ref "R1") (pin "2") (pinfunction "2_2") (pintype "passive"))
      (node (ref "R24") (pin "1") (pinfunction "1_1") (pintype "passive"))
      (node (ref "R31") (pin "2") (pinfunction "2_2") (pintype "passive"))
      (node (ref "R37") (pin "2") (pinfunction "2_2") (pintype "passive"))
      (node (ref "R38") (pin "2") (pinfunction "2_2") (pintype "passive"))
      (node (ref "R39") (pin "1") (pinfunction "1_1") (pintype "passive"))
      (node (ref "R48") (pin "1") (pinfunction "1_1") (pintype "passive"))
      (node (ref "R49") (pin "1") (pinfunction "1_1") (pintype "passive"))
      (node (ref "R5") (pin "2") (pinfunction "2_2") (pintype "passive"))
      (node (ref "R50") (pin "1") (pinfunction "1_1") (pintype "passive"))
      (node (ref "R54") (pin "1") (pinfunction "1_1") (pintype "passive"))
      (node (ref "R60") (pin "1") (pinfunction "1_1") (pintype "passive"))
      (node (ref "R7") (pin "1") (pinfunction "1_1") (pintype "passive"))
      (node (ref "R85") (pin "1") (pinfunction "1_1") (pintype "passive"))
      (node (ref "R9") (pin "2") (pinfunction "2_2") (pintype "passive"))
      (node (ref "U1") (pin "A13") (pinfunction "VREFN_0_A13") (pintype "input"))
      (node (ref "U1") (pin "B12") (pinfunction "VREFP_0_B12") (pintype "input"))
      (node (ref "U1") (pin "B13") (pinfunction "VN_0_B13") (pintype "input"))
      (node (ref "U1") (pin "E18") (pinfunction "IO_L3P_T0_DQS_PUDC_B_14_E18") (pintype "bidirectional"))
      (node (ref "U1") (pin "U10") (pinfunction "M2_0_U10") (pintype "input"))
      (node (ref "U1") (pin "W11") (pinfunction "M1_0_W11") (pintype "input"))
      (node (ref "U10") (pin "4") (pinfunction "G_4") (pintype "passive"))
      (node (ref "U11") (pin "0") (pinfunction "GND_0") (pintype "passive"))
      (node (ref "U11") (pin "10") (pinfunction "GND_10") (pintype "passive"))
      (node (ref "U12") (pin "2") (pinfunction "GND_2") (pintype "passive"))
      (node (ref "U13") (pin "1") (pinfunction "GND_1") (pintype "passive"))
      (node (ref "U13") (pin "16") (pinfunction "GND_16") (pintype "passive"))
      (node (ref "U13") (pin "2") (pinfunction "GND_2") (pintype "passive"))
      (node (ref "U13") (pin "4") (pinfunction "GND_4") (pintype "passive"))
      (node (ref "U13") (pin "5") (pinfunction "GND_5") (pintype "passive"))
      (node (ref "U15") (pin "B2") (pinfunction "G_B2") (pintype "passive"))
      (node (ref "U16") (pin "B2") (pinfunction "G_B2") (pintype "passive"))
      (node (ref "U17") (pin "B2") (pinfunction "G_B2") (pintype "passive"))
      (node (ref "U27") (pin "B2") (pinfunction "G_B2") (pintype "passive"))
      (node (ref "U3") (pin "C3") (pinfunction "GND_C3") (pintype "passive"))
      (node (ref "U30") (pin "10") (pinfunction "GND_10") (pintype "passive"))
      (node (ref "U4") (pin "B3") (pinfunction "VSS_B3") (pintype "passive"))
      (node (ref "U4'") (pin "B3") (pinfunction "VSS_B3") (pintype "passive"))
      (node (ref "U5") (pin "3") (pinfunction "GND_3") (pintype "passive"))
      (node (ref "U6") (pin "A2") (pinfunction "GND_A2") (pintype "passive"))
      (node (ref "U7") (pin "2") (pinfunction "GND_2") (pintype "passive"))
      (node (ref "U8") (pin "2") (pinfunction "GND_2") (pintype "passive"))
      (node (ref "U9") (pin "B1") (pinfunction "GND_B1") (pintype "passive"))
      (node (ref "X10") (pin "0") (pinfunction "GND_0") (pintype "passive"))
      (node (ref "X10") (pin "15") (pinfunction "GND_15") (pintype "passive"))
      (node (ref "X10") (pin "18") (pinfunction "GND_18") (pintype "passive"))
      (node (ref "X10") (pin "21") (pinfunction "GND_21") (pintype "passive"))
      (node (ref "X10") (pin "26") (pinfunction "GND_26") (pintype "passive"))
      (node (ref "X10") (pin "27") (pinfunction "GND_27") (pintype "passive"))
      (node (ref "X10") (pin "29") (pinfunction "GND_29") (pintype "passive"))
      (node (ref "X10") (pin "34") (pinfunction "GND_34") (pintype "passive"))
      (node (ref "X10") (pin "35") (pinfunction "GND_35") (pintype "passive"))
      (node (ref "X10") (pin "37") (pinfunction "Reserved_37") (pintype "passive"))
      (node (ref "X10") (pin "4") (pinfunction "GND_4") (pintype "passive"))
      (node (ref "X10") (pin "40") (pinfunction "GND_40") (pintype "passive"))
      (node (ref "X10") (pin "43") (pinfunction "Reserved_43") (pintype "passive"))
      (node (ref "X10") (pin "50") (pinfunction "GND_50") (pintype "passive"))
      (node (ref "X10") (pin "9") (pinfunction "GND_9") (pintype "passive"))
      (node (ref "X11") (pin "0") (pinfunction "GND_0") (pintype "passive"))
      (node (ref "X11") (pin "5") (pinfunction "GND_5") (pintype "passive"))
      (node (ref "X12") (pin "0") (pintype "passive"))
      (node (ref "X12") (pin "3") (pintype "passive"))
      (node (ref "X12") (pin "5") (pintype "passive"))
      (node (ref "X12") (pin "7") (pintype "passive"))
      (node (ref "X13") (pin "0") (pintype "passive"))
      (node (ref "X13") (pin "1") (pintype "passive"))
      (node (ref "X13") (pin "12") (pintype "passive"))
      (node (ref "X13") (pin "15") (pintype "passive"))
      (node (ref "X13") (pin "4") (pintype "passive"))
      (node (ref "X13") (pin "7") (pintype "passive"))
      (node (ref "X13") (pin "9") (pintype "passive"))
      (node (ref "X8") (pin "0") (pintype "passive"))
      (node (ref "X8") (pin "1") (pintype "passive"))
      (node (ref "X8") (pin "12") (pintype "passive"))
      (node (ref "X8") (pin "15") (pintype "passive"))
      (node (ref "X8") (pin "4") (pintype "passive"))
      (node (ref "X8") (pin "7") (pintype "passive"))
      (node (ref "X8") (pin "9") (pintype "passive"))
      (node (ref "X9") (pin "6") (pinfunction "GND_6") (pintype "passive"))
    )
    (net (code "181") (name "Net-(C17-Pad1)") (class "Default")
      (node (ref "C17") (pin "1") (pinfunction "1_1") (pintype "passive"))
      (node (ref "R39") (pin "2") (pinfunction "2_2") (pintype "passive"))
      (node (ref "R40") (pin "1") (pinfunction "1_1") (pintype "passive"))
      (node (ref "R41") (pin "1") (pinfunction "1_1") (pintype "passive"))
      (node (ref "R42") (pin "2") (pinfunction "2_2") (pintype "passive"))
    )
    (net (code "182") (name "Net-(J5-Pad1)") (class "Default")
      (node (ref "J5") (pin "1") (pinfunction "1_1") (pintype "passive"))
      (node (ref "X10") (pin "45") (pinfunction "Reserved_45") (pintype "passive"))
    )
    (net (code "183") (name "Net-(J8-Pad1)") (class "Default")
      (node (ref "J8") (pin "1") (pinfunction "1_1") (pintype "passive"))
      (node (ref "X10") (pin "51") (pinfunction "Reserved_51") (pintype "passive"))
    )
    (net (code "184") (name "Net-(LED1-A)") (class "Default")
      (node (ref "LED1") (pin "2") (pinfunction "A_2") (pintype "passive"))
      (node (ref "R44") (pin "1") (pinfunction "1_1") (pintype "passive"))
    )
    (net (code "185") (name "Net-(LED2-A)") (class "Default")
      (node (ref "LED2") (pin "2") (pinfunction "A_2") (pintype "passive"))
      (node (ref "R43") (pin "2") (pinfunction "2_2") (pintype "passive"))
    )
    (net (code "186") (name "Net-(U1E-VP_0)") (class "Default")
      (node (ref "C12") (pin "2") (pinfunction "2_2") (pintype "passive"))
      (node (ref "R36") (pin "1") (pinfunction "1_1") (pintype "passive"))
      (node (ref "R36`") (pin "1") (pinfunction "1_1") (pintype "passive"))
      (node (ref "R38") (pin "1") (pinfunction "1_1") (pintype "passive"))
      (node (ref "U1") (pin "A12") (pinfunction "VP_0_A12") (pintype "input"))
    )
    (net (code "187") (name "Net-(U2A-FCLK1)") (class "Default")
      (node (ref "R2") (pin "2") (pinfunction "2_2") (pintype "passive"))
      (node (ref "U2") (pin "AA33") (pinfunction "FCLK1_AA33") (pintype "passive"))
    )
    (net (code "188") (name "Net-(U2A-FCLK2)") (class "Default")
      (node (ref "R3") (pin "1") (pinfunction "1_1") (pintype "passive"))
      (node (ref "U2") (pin "R29") (pinfunction "FCLK2_R29") (pintype "passive"))
    )
    (net (code "189") (name "Net-(U2A-TXPLLCLK)") (class "Default")
      (node (ref "R15") (pin "1") (pinfunction "1_1") (pintype "passive"))
      (node (ref "U2") (pin "E5") (pinfunction "TXPLLCLK_E5") (pintype "passive"))
    )
    (net (code "190") (name "Net-(U2C-VR_10K)") (class "Default")
      (node (ref "R1") (pin "1") (pinfunction "1_1") (pintype "passive"))
      (node (ref "U2") (pin "F18") (pinfunction "VR_10K_F18") (pintype "passive"))
    )
    (net (code "191") (name "Net-(U3-CLKOUT)") (class "Default")
      (node (ref "R16") (pin "1") (pinfunction "1_1") (pintype "passive"))
      (node (ref "U3") (pin "A5") (pinfunction "CLKOUT_A5") (pintype "passive"))
    )
    (net (code "192") (name "Net-(U3-RBIAS)") (class "Default")
      (node (ref "R9") (pin "1") (pinfunction "1_1") (pintype "passive"))
      (node (ref "U3") (pin "A1") (pinfunction "RBIAS_A1") (pintype "passive"))
    )
    (net (code "193") (name "Net-(U3-REFSEL0)") (class "Default")
      (node (ref "R6") (pin "2") (pinfunction "2_2") (pintype "passive"))
      (node (ref "R7") (pin "2") (pinfunction "2_2") (pintype "passive"))
      (node (ref "U3") (pin "E2") (pinfunction "REFSEL0_E2") (pintype "passive"))
    )
    (net (code "194") (name "Net-(U3-VBUS)") (class "Default")
      (node (ref "R8") (pin "2") (pinfunction "2_2") (pintype "passive"))
      (node (ref "U3") (pin "D2") (pinfunction "VBUS_D2") (pintype "passive"))
    )
    (net (code "195") (name "Net-(U3-VDD1.8)") (class "Default")
      (node (ref "C4") (pin "2") (pinfunction "2_2") (pintype "passive"))
      (node (ref "U3") (pin "B2") (pinfunction "VDD1.8_B2") (pintype "passive"))
    )
    (net (code "196") (name "Net-(U4'-DQ0)") (class "Default")
      (node (ref "R18") (pin "2") (pinfunction "2_2") (pintype "passive"))
      (node (ref "U4") (pin "D3") (pinfunction "DQ0_D3") (pintype "passive"))
      (node (ref "U4'") (pin "D3") (pinfunction "DQ0_D3") (pintype "passive"))
    )
    (net (code "197") (name "Net-(U4'-DQ1)") (class "Default")
      (node (ref "R10") (pin "1") (pinfunction "1_1") (pintype "passive"))
      (node (ref "U4") (pin "D2") (pinfunction "DQ1_D2") (pintype "passive"))
      (node (ref "U4'") (pin "D2") (pinfunction "DQ1_D2") (pintype "passive"))
    )
    (net (code "198") (name "Net-(U4'-DQ2)") (class "Default")
      (node (ref "R11") (pin "1") (pinfunction "1_1") (pintype "passive"))
      (node (ref "R13") (pin "1") (pinfunction "1_1") (pintype "passive"))
      (node (ref "U4") (pin "C4") (pinfunction "DQ2_C4") (pintype "passive"))
      (node (ref "U4'") (pin "C4") (pinfunction "DQ2_C4") (pintype "passive"))
    )
    (net (code "199") (name "Net-(U4'-DQ3)") (class "Default")
      (node (ref "R14") (pin "1") (pinfunction "1_1") (pintype "passive"))
      (node (ref "R17") (pin "2") (pinfunction "2_2") (pintype "passive"))
      (node (ref "U4") (pin "D4") (pinfunction "DQ3_D4") (pintype "passive"))
      (node (ref "U4'") (pin "D4") (pinfunction "DQ3_D4") (pintype "passive"))
    )
    (net (code "200") (name "Net-(U5-I2C{slash}~{SPI})") (class "Default")
      (node (ref "R25") (pin "2") (pinfunction "2_2") (pintype "passive"))
      (node (ref "U5") (pin "4") (pinfunction "I2C/~{SPI}_4") (pintype "passive"))
    )
    (net (code "201") (name "Net-(U5-VDD)") (class "Default")
      (node (ref "C8") (pin "2") (pinfunction "2_2") (pintype "passive"))
      (node (ref "C9") (pin "2") (pinfunction "2_2") (pintype "passive"))
      (node (ref "L1") (pin "1") (pinfunction "1_1") (pintype "passive"))
      (node (ref "R25") (pin "1") (pinfunction "1_1") (pintype "passive"))
      (node (ref "U5") (pin "1") (pinfunction "VDD_1") (pintype "passive"))
    )
    (net (code "202") (name "Net-(U5-VOUT)") (class "Default")
      (node (ref "R32") (pin "1") (pinfunction "1_1") (pintype "passive"))
      (node (ref "U5") (pin "2") (pinfunction "VOUT_2") (pintype "passive"))
    )
    (net (code "203") (name "Net-(U5-VREF)") (class "Default")
      (node (ref "C219") (pin "2") (pinfunction "2_2") (pintype "passive"))
      (node (ref "U5") (pin "8") (pinfunction "VREF_8") (pintype "passive"))
    )
    (net (code "204") (name "Net-(U6-Vcc)") (class "Default")
      (node (ref "C10") (pin "1") (pinfunction "1_1") (pintype "passive"))
      (node (ref "R34") (pin "1") (pinfunction "1_1") (pintype "passive"))
      (node (ref "U6") (pin "A1") (pinfunction "Vcc_A1") (pintype "passive"))
    )
    (net (code "205") (name "Net-(U7-Fo)") (class "Default")
      (node (ref "C19") (pin "1") (pinfunction "1_1") (pintype "passive"))
      (node (ref "U7") (pin "3") (pinfunction "Fo_3") (pintype "passive"))
      (node (ref "U8") (pin "3") (pinfunction "Fo_3") (pintype "passive"))
    )
    (net (code "206") (name "Net-(U7-Vt)") (class "Default")
      (node (ref "C13") (pin "2") (pinfunction "2_2") (pintype "passive"))
      (node (ref "R32") (pin "2") (pinfunction "2_2") (pintype "passive"))
      (node (ref "R37") (pin "1") (pinfunction "1_1") (pintype "passive"))
      (node (ref "U7") (pin "1") (pinfunction "Vt_1") (pintype "power_in"))
      (node (ref "U8") (pin "1") (pinfunction "Vt_1") (pintype "power_in"))
    )
    (net (code "207") (name "Net-(U9-Vin)") (class "Default")
      (node (ref "C16") (pin "2") (pinfunction "2_2") (pintype "passive"))
      (node (ref "L2") (pin "2") (pinfunction "2_2") (pintype "passive"))
      (node (ref "U9") (pin "A2") (pinfunction "Vin_A2") (pintype "passive"))
    )
    (net (code "208") (name "Net-(U10-+V)") (class "Default")
      (node (ref "C18") (pin "1") (pinfunction "1_1") (pintype "passive"))
      (node (ref "C26") (pin "1") (pinfunction "1_1") (pintype "passive"))
      (node (ref "L3") (pin "2") (pinfunction "2_2") (pintype "passive"))
      (node (ref "R40") (pin "2") (pinfunction "2_2") (pintype "passive"))
      (node (ref "U10") (pin "8") (pinfunction "+V_8") (pintype "passive"))
      (node (ref "U12") (pin "5") (pinfunction "VCC_5") (pintype "passive"))
    )
    (net (code "209") (name "Net-(U10-A1)") (class "Default")
      (node (ref "R42") (pin "1") (pinfunction "1_1") (pintype "passive"))
      (node (ref "U10") (pin "5") (pinfunction "A2_5") (pintype "passive"))
      (node (ref "U10") (pin "7") (pinfunction "A1_7") (pintype "passive"))
      (node (ref "U12") (pin "4") (pinfunction "A_4") (pintype "passive"))
    )
    (net (code "210") (name "Net-(U10-A3)") (class "Default")
      (node (ref "C19") (pin "2") (pinfunction "2_2") (pintype "passive"))
      (node (ref "R41") (pin "2") (pinfunction "2_2") (pintype "passive"))
      (node (ref "U10") (pin "2") (pinfunction "A3_2") (pintype "passive"))
    )
    (net (code "211") (name "Net-(U10-Y2)") (class "Default")
      (node (ref "C14") (pin "1") (pinfunction "1_1") (pintype "passive"))
      (node (ref "U10") (pin "3") (pinfunction "Y2_3") (pintype "passive"))
    )
    (net (code "212") (name "Net-(U12-B1)") (class "Default")
      (node (ref "C28") (pin "1") (pinfunction "1_1") (pintype "passive"))
      (node (ref "U12") (pin "1") (pinfunction "B1_1") (pintype "passive"))
    )
    (net (code "213") (name "Net-(U13-LED)") (class "Default")
      (node (ref "R44") (pin "2") (pinfunction "2_2") (pintype "passive"))
      (node (ref "U13") (pin "13") (pinfunction "LED_13") (pintype "passive"))
    )
    (net (code "214") (name "Net-(U13-RX_in)") (class "Default")
      (node (ref "L6") (pin "2") (pinfunction "2_2") (pintype "passive"))
      (node (ref "U13") (pin "9") (pinfunction "RX_in_9") (pintype "passive"))
    )
    (net (code "215") (name "Net-(U13-TX_out)") (class "Default")
      (node (ref "L5") (pin "2") (pinfunction "2_2") (pintype "passive"))
      (node (ref "U13") (pin "10") (pinfunction "TX_out_10") (pintype "passive"))
    )
    (net (code "216") (name "Net-(U27-OUT)") (class "Default")
      (node (ref "C15") (pin "2") (pinfunction "2_2") (pintype "passive"))
      (node (ref "U27") (pin "A2") (pinfunction "OUT_A2") (pintype "passive"))
      (node (ref "U7") (pin "4") (pinfunction "VCC_4") (pintype "power_in"))
      (node (ref "U8") (pin "4") (pinfunction "VCC_4") (pintype "power_in"))
    )
    (net (code "217") (name "Net-(U30-+VCC)") (class "Default")
      (node (ref "C220") (pin "2") (pinfunction "2_2") (pintype "passive"))
      (node (ref "L74") (pin "2") (pinfunction "2_2") (pintype "passive"))
      (node (ref "U30") (pin "5") (pinfunction "+VCC_5") (pintype "passive"))
    )
    (net (code "218") (name "Net-(U30-A1)") (class "Default")
      (node (ref "J9") (pin "1") (pinfunction "1_1") (pintype "passive"))
      (node (ref "J9") (pin "2") (pinfunction "2_2") (pintype "passive"))
      (node (ref "U30") (pin "6") (pinfunction "A1_6") (pintype "passive"))
      (node (ref "X10") (pin "30") (pinfunction "SMB_CLK_30") (pintype "passive"))
    )
    (net (code "219") (name "Net-(U30-B1)") (class "Default")
      (node (ref "J10") (pin "1") (pinfunction "1_1") (pintype "passive"))
      (node (ref "J10") (pin "2") (pinfunction "2_2") (pintype "passive"))
      (node (ref "U30") (pin "4") (pinfunction "B1_4") (pintype "passive"))
      (node (ref "X10") (pin "32") (pinfunction "SMB_DATA_32") (pintype "passive"))
    )
    (net (code "220") (name "Net-(X11-V_BUS)") (class "Default")
      (node (ref "L7") (pin "1") (pinfunction "1_1") (pintype "passive"))
      (node (ref "X11") (pin "1") (pinfunction "V_BUS_1") (pintype "power_in"))
    )
    (net (code "221") (name "unconnected-(U1A-IO_L7N_T1_D10_14-PadJ18)") (class "Default")
      (node (ref "U1") (pin "J18") (pinfunction "IO_L7N_T1_D10_14_J18") (pintype "bidirectional+no_connect"))
    )
    (net (code "222") (name "unconnected-(U1A-IO_L8N_T1_D12_14-PadK18)") (class "Default")
      (node (ref "U1") (pin "K18") (pinfunction "IO_L8N_T1_D12_14_K18") (pintype "bidirectional+no_connect"))
    )
    (net (code "223") (name "unconnected-(U1A-IO_L14N_T2_SRCC_14-PadR18)") (class "Default")
      (node (ref "U1") (pin "R18") (pinfunction "IO_L14N_T2_SRCC_14_R18") (pintype "bidirectional+no_connect"))
    )
    (net (code "224") (name "unconnected-(U1A-IO_L14P_T2_SRCC_14-PadP18)") (class "Default")
      (node (ref "U1") (pin "P18") (pinfunction "IO_L14P_T2_SRCC_14_P18") (pintype "bidirectional+no_connect"))
    )
    (net (code "225") (name "unconnected-(U1A-IO_L17N_T2_A13_D29_14-PadT18)") (class "Default")
      (node (ref "U1") (pin "T18") (pinfunction "IO_L17N_T2_A13_D29_14_T18") (pintype "bidirectional+no_connect"))
    )
    (net (code "226") (name "unconnected-(U1A-IO_L18N_T2_A11_D27_14-PadU18)") (class "Default")
      (node (ref "U1") (pin "U18") (pinfunction "IO_L18N_T2_A11_D27_14_U18") (pintype "bidirectional+no_connect"))
    )
    (net (code "227") (name "unconnected-(U1A-IO_L24P_T3_A01_D17_14-PadV13)") (class "Default")
      (node (ref "U1") (pin "V13") (pinfunction "IO_L24P_T3_A01_D17_14_V13") (pintype "bidirectional+no_connect"))
    )
    (net (code "228") (name "unconnected-(U1E-DXN_0-PadB11)") (class "Default")
      (node (ref "U1") (pin "B11") (pinfunction "DXN_0_B11") (pintype "input+no_connect"))
    )
    (net (code "229") (name "unconnected-(U1E-DXP_0-PadA11)") (class "Default")
      (node (ref "U1") (pin "A11") (pinfunction "DXP_0_A11") (pintype "input+no_connect"))
    )
    (net (code "230") (name "unconnected-(U2A-LOGIC_RST-PadV30)") (class "Default")
      (node (ref "U2") (pin "V30") (pinfunction "LOGIC_RST_V30") (pintype "passive+no_connect"))
    )
    (net (code "231") (name "unconnected-(U2A-RXPLLCLK-PadAM24)") (class "Default")
      (node (ref "U2") (pin "AM24") (pinfunction "RXPLLCLK_AM24") (pintype "passive+no_connect"))
    )
    (net (code "232") (name "unconnected-(U2A-SCL-PadC27)") (class "Default")
      (node (ref "U2") (pin "C27") (pinfunction "SCL_C27") (pintype "passive+no_connect"))
    )
    (net (code "233") (name "unconnected-(U2A-SDA-PadD26)") (class "Default")
      (node (ref "U2") (pin "D26") (pinfunction "SDA_D26") (pintype "passive+no_connect"))
    )
    (net (code "234") (name "unconnected-(U2C-RXOUTIN_1-PadAB2)") (class "Default")
      (node (ref "U2") (pin "AB2") (pinfunction "RXOUTIN_1_AB2") (pintype "passive+no_connect"))
    )
    (net (code "235") (name "unconnected-(U2C-RXOUTIN_2-PadAC3)") (class "Default")
      (node (ref "U2") (pin "AC3") (pinfunction "RXOUTIN_2_AC3") (pintype "passive+no_connect"))
    )
    (net (code "236") (name "unconnected-(U2C-RXOUTIP_1-PadY6)") (class "Default")
      (node (ref "U2") (pin "Y6") (pinfunction "RXOUTIP_1_Y6") (pintype "passive+no_connect"))
    )
    (net (code "237") (name "unconnected-(U2C-RXOUTIP_2-PadAD2)") (class "Default")
      (node (ref "U2") (pin "AD2") (pinfunction "RXOUTIP_2_AD2") (pintype "passive+no_connect"))
    )
    (net (code "238") (name "unconnected-(U2C-RXOUTQN_1-PadAA5)") (class "Default")
      (node (ref "U2") (pin "AA5") (pinfunction "RXOUTQN_1_AA5") (pintype "passive+no_connect"))
    )
    (net (code "239") (name "unconnected-(U2C-RXOUTQN_2-PadAB6)") (class "Default")
      (node (ref "U2") (pin "AB6") (pinfunction "RXOUTQN_2_AB6") (pintype "passive+no_connect"))
    )
    (net (code "240") (name "unconnected-(U2C-RXOUTQP_1-PadAB4)") (class "Default")
      (node (ref "U2") (pin "AB4") (pinfunction "RXOUTQP_1_AB4") (pintype "passive+no_connect"))
    )
    (net (code "241") (name "unconnected-(U2C-RXOUTQP_2-PadAC5)") (class "Default")
      (node (ref "U2") (pin "AC5") (pinfunction "RXOUTQP_2_AC5") (pintype "passive+no_connect"))
    )
    (net (code "242") (name "unconnected-(U4'-RST#-PadA4)") (class "Default")
      (node (ref "U4'") (pin "A4") (pinfunction "RST#_A4") (pintype "passive+no_connect"))
    )
    (net (code "243") (name "unconnected-(U4-RST#-PadA4)") (class "Default")
      (node (ref "U4") (pin "A4") (pinfunction "RST#_A4") (pintype "passive+no_connect"))
    )
    (net (code "244") (name "unconnected-(U6-ALRT-PadC1)") (class "Default")
      (node (ref "U6") (pin "C1") (pinfunction "ALRT_C1") (pintype "passive+no_connect"))
    )
    (net (code "245") (name "unconnected-(U13-E2-Pad11)") (class "Default")
      (node (ref "U13") (pin "11") (pinfunction "E2_11") (pintype "passive+no_connect"))
    )
    (net (code "246") (name "unconnected-(U13-E3-Pad12)") (class "Default")
      (node (ref "U13") (pin "12") (pinfunction "E3_12") (pintype "passive+no_connect"))
    )
    (net (code "247") (name "unconnected-(U13-HW_R-Pad7)") (class "Default")
      (node (ref "U13") (pin "7") (pinfunction "HW_R_7") (pintype "passive+no_connect"))
    )
    (net (code "248") (name "unconnected-(U13-HW_S-Pad8)") (class "Default")
      (node (ref "U13") (pin "8") (pinfunction "HW_S_8") (pintype "passive+no_connect"))
    )
    (net (code "249") (name "unconnected-(U30-A0-Pad9)") (class "Default")
      (node (ref "U30") (pin "9") (pinfunction "A0_9") (pintype "passive+no_connect"))
    )
    (net (code "250") (name "unconnected-(U30-B0-Pad1)") (class "Default")
      (node (ref "U30") (pin "1") (pinfunction "B0_1") (pintype "passive+no_connect"))
    )
    (net (code "251") (name "unconnected-(X10-+1.5V-Pad6)") (class "Default")
      (node (ref "X10") (pin "6") (pinfunction "+1.5V_6") (pintype "passive+no_connect"))
    )
    (net (code "252") (name "unconnected-(X10-+1.5V-Pad28)") (class "Default")
      (node (ref "X10") (pin "28") (pinfunction "+1.5V_28") (pintype "passive+no_connect"))
    )
    (net (code "253") (name "unconnected-(X10-+1.5V-Pad48)") (class "Default")
      (node (ref "X10") (pin "48") (pinfunction "+1.5V_48") (pintype "passive+no_connect"))
    )
    (net (code "254") (name "unconnected-(X10-+3.3Vaux-Pad24)") (class "Default")
      (node (ref "X10") (pin "24") (pinfunction "+3.3Vaux_24") (pintype "passive+no_connect"))
    )
    (net (code "255") (name "unconnected-(X10-UIM_VPP-Pad16)") (class "Default")
      (node (ref "X10") (pin "16") (pinfunction "UIM_VPP_16") (pintype "passive+no_connect"))
    )
    (net (code "256") (name "unconnected-(X10-WAKE#-Pad1)") (class "Default")
      (node (ref "X10") (pin "1") (pinfunction "WAKE#_1") (pintype "passive+no_connect"))
    )
    (net (code "257") (name "unconnected-(X11-ID-Pad4)") (class "Default")
      (node (ref "X11") (pin "4") (pinfunction "ID_4") (pintype "passive+no_connect"))
    )
  )
)
